# Vorlage_ATmega2560-16AU.net
KiCad netlist of a schematic drawn in EAGLE
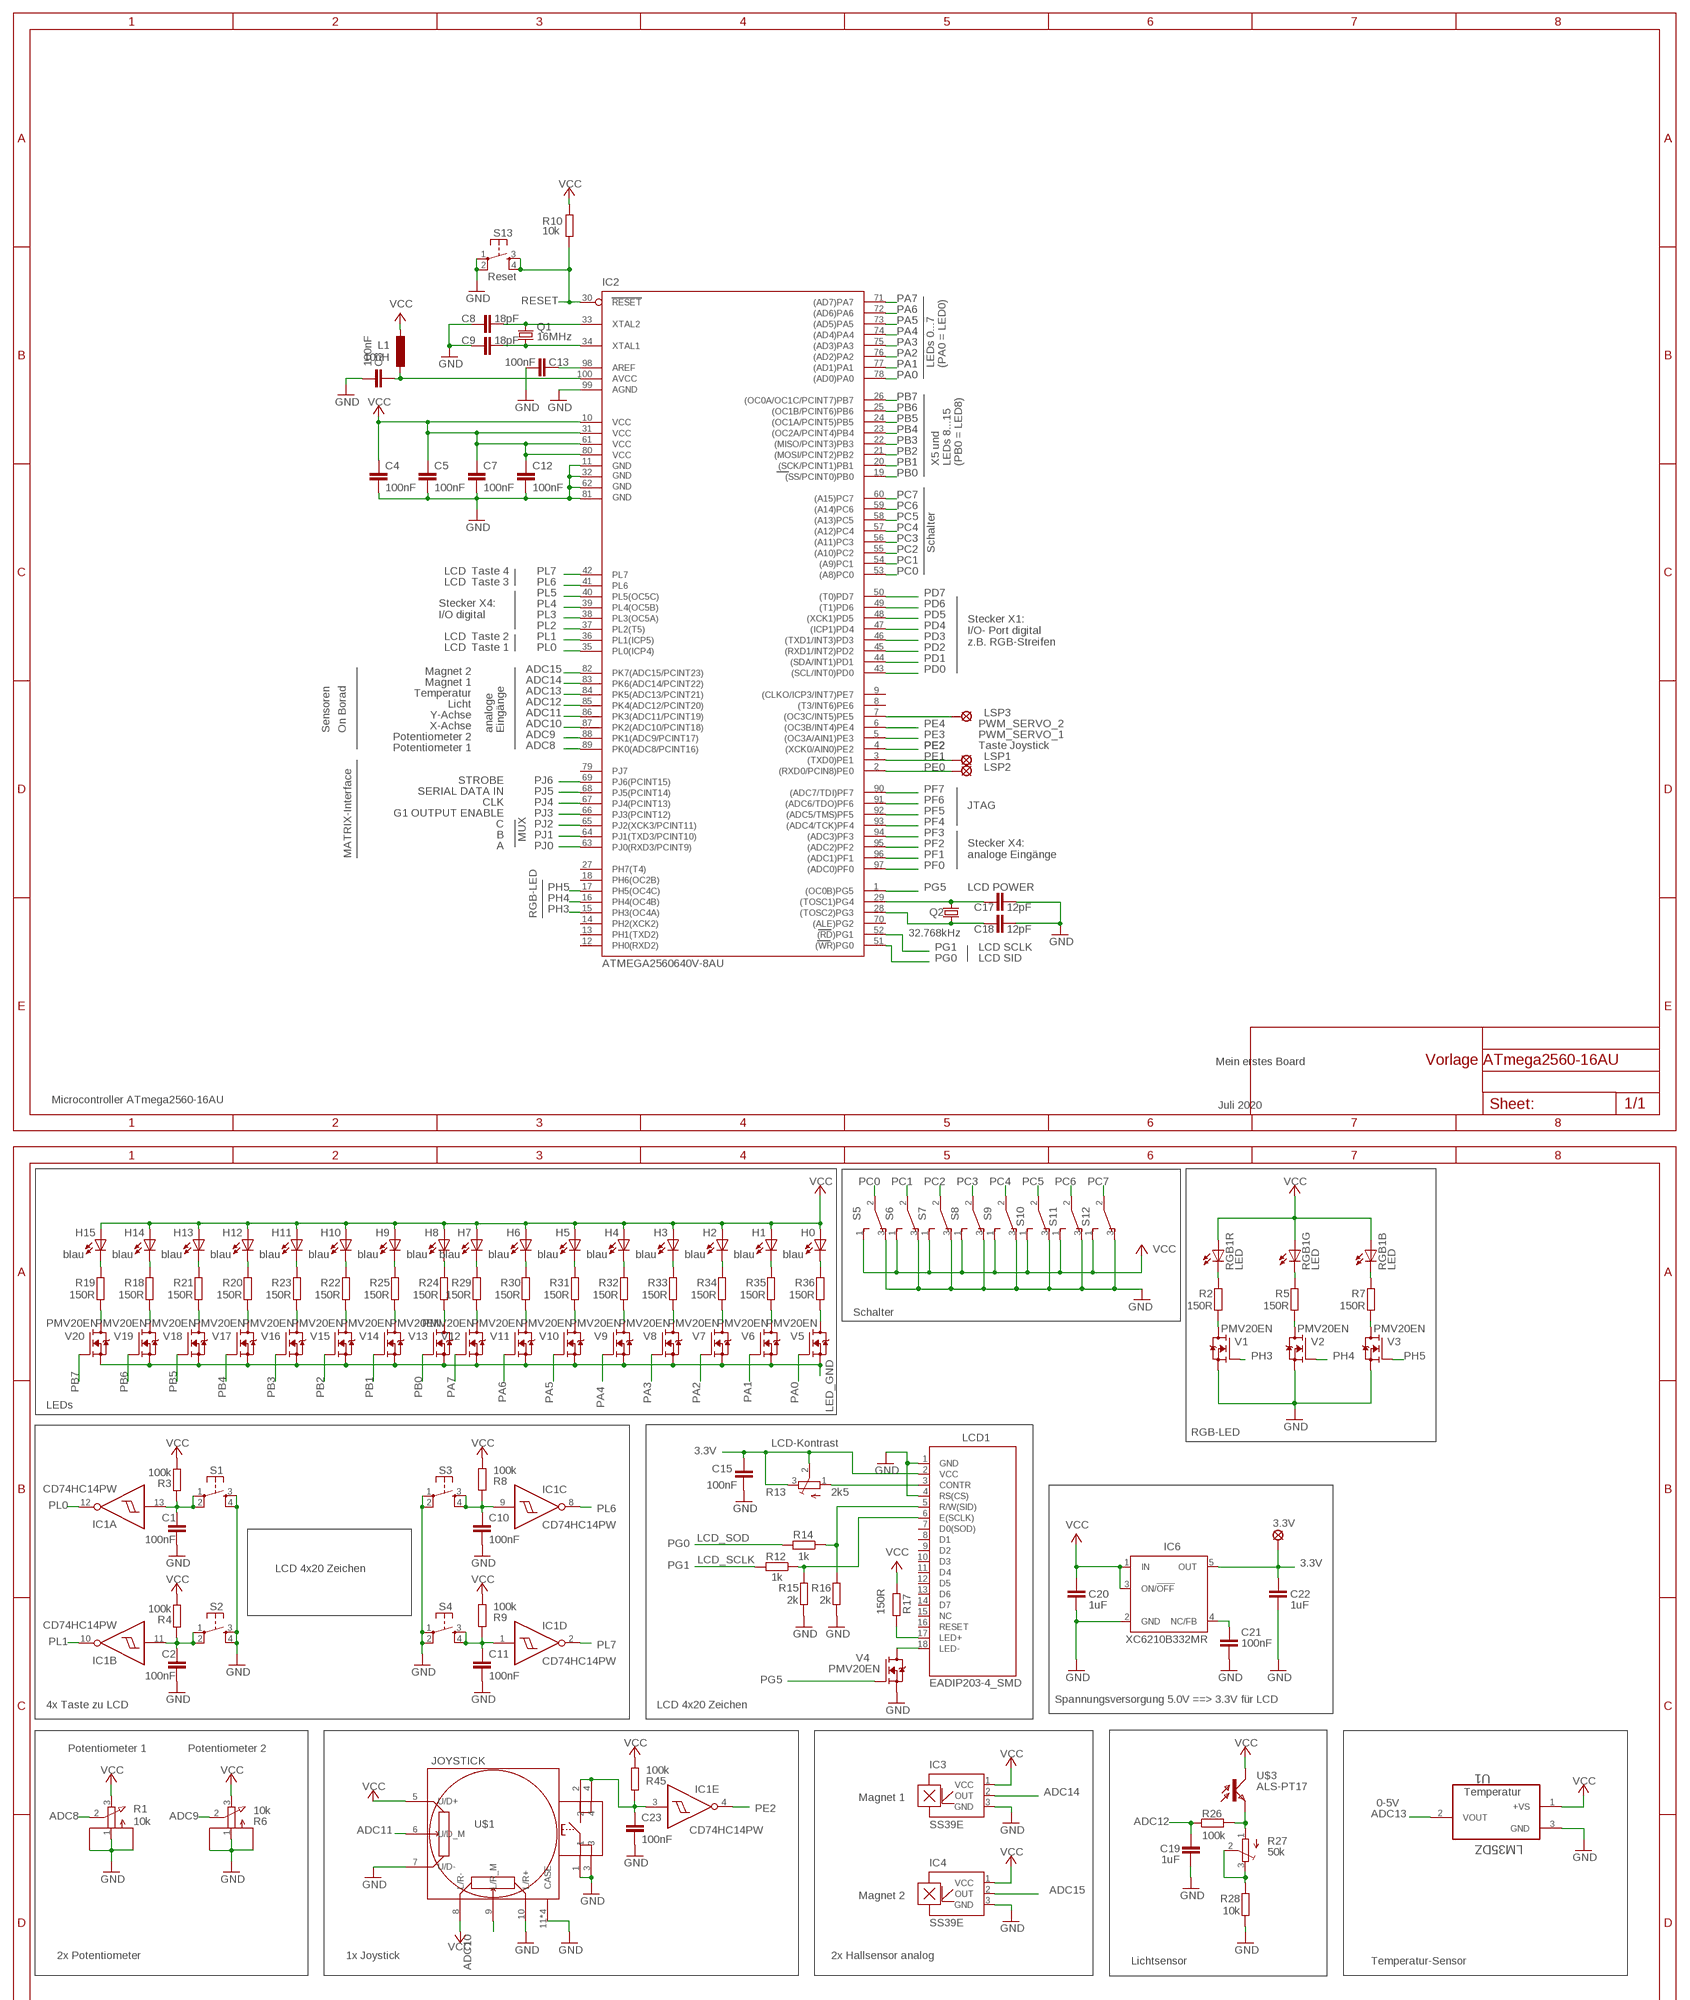
[diagram p0: schematic, sheet 1, part 1 of 2]
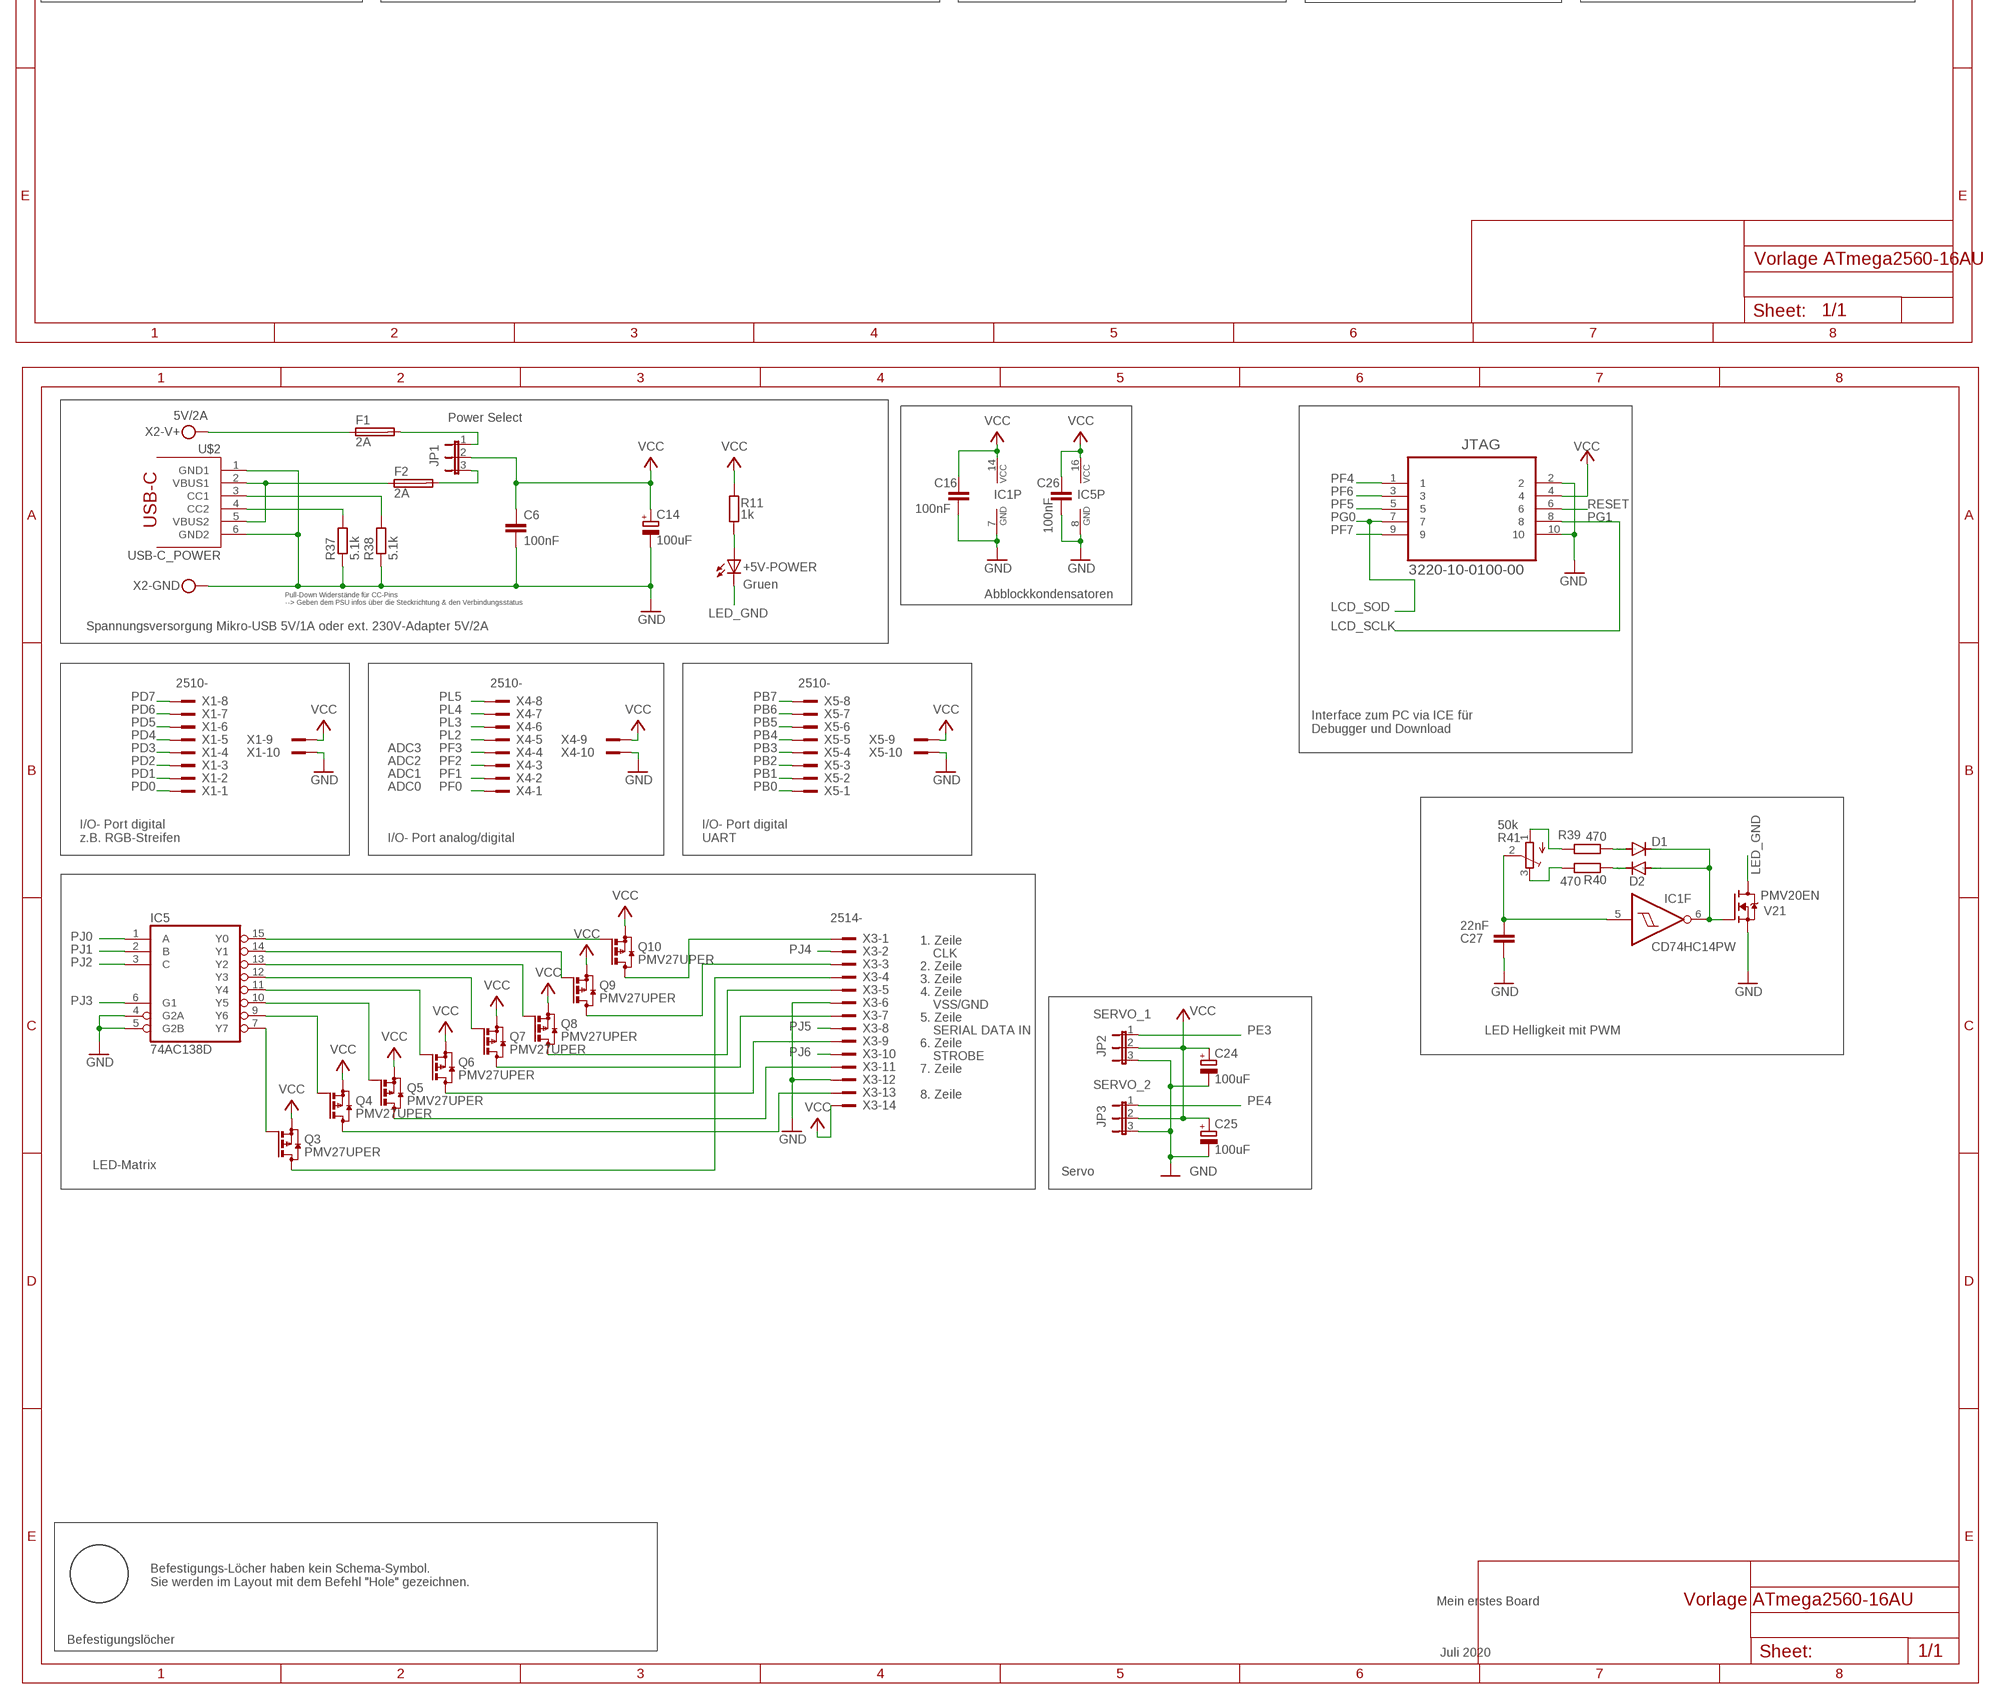
[diagram p1: schematic, sheet 1, part 2 of 2]

(export (version "E")
  (design (tool "Eeschema 10.0.6"))
  (components
    (comp (ref "+5V-POWER")
      (value "Gruen")
      (footprint "eagle-import:CHIPLED_1206")
      (libsource (lib "eagle-import") (part "LEDCHIPLED_1206"))
    )
    (comp (ref "3.3V")
      (value "3.3V")
      (footprint "eagle-import:LSP11")
      (libsource (lib "eagle-import") (part "LSP11"))
    )
    (comp (ref "C1")
      (value "100nF")
      (footprint "eagle-import:C1206")
      (libsource (lib "eagle-import") (part "C-EUC1206"))
    )
    (comp (ref "C2")
      (value "100nF")
      (footprint "eagle-import:C1206")
      (libsource (lib "eagle-import") (part "C-EUC1206"))
    )
    (comp (ref "C3")
      (value "100nF")
      (footprint "eagle-import:C1206")
      (libsource (lib "eagle-import") (part "C-EUC1206"))
    )
    (comp (ref "C4")
      (value "100nF")
      (footprint "eagle-import:C1206")
      (libsource (lib "eagle-import") (part "C-EUC1206"))
    )
    (comp (ref "C5")
      (value "100nF")
      (footprint "eagle-import:C1206")
      (libsource (lib "eagle-import") (part "C-EUC1206"))
    )
    (comp (ref "C6")
      (value "100nF")
      (footprint "eagle-import:C1206")
      (libsource (lib "eagle-import") (part "C-EUC1206"))
    )
    (comp (ref "C7")
      (value "100nF")
      (footprint "eagle-import:C1206")
      (libsource (lib "eagle-import") (part "C-EUC1206"))
    )
    (comp (ref "C8")
      (value "18pF")
      (footprint "eagle-import:C0805K")
      (libsource (lib "eagle-import") (part "C-EUC0805K"))
    )
    (comp (ref "C9")
      (value "18pF")
      (footprint "eagle-import:C0805K")
      (libsource (lib "eagle-import") (part "C-EUC0805K"))
    )
    (comp (ref "C10")
      (value "100nF")
      (footprint "eagle-import:C1206")
      (libsource (lib "eagle-import") (part "C-EUC1206"))
    )
    (comp (ref "C11")
      (value "100nF")
      (footprint "eagle-import:C1206")
      (libsource (lib "eagle-import") (part "C-EUC1206"))
    )
    (comp (ref "C12")
      (value "100nF")
      (footprint "eagle-import:C1206")
      (libsource (lib "eagle-import") (part "C-EUC1206"))
    )
    (comp (ref "C13")
      (value "100nF")
      (footprint "eagle-import:C1206")
      (libsource (lib "eagle-import") (part "C-EUC1206"))
    )
    (comp (ref "C14")
      (value "100uF")
      (footprint "eagle-import:UD-6,3X5,8_NICHICON")
      (libsource (lib "eagle-import") (part "CPOL-EUUD-6,3X8,8"))
    )
    (comp (ref "C15")
      (value "100nF")
      (footprint "eagle-import:C1206")
      (libsource (lib "eagle-import") (part "C-EUC1206"))
    )
    (comp (ref "C16")
      (value "100nF")
      (footprint "eagle-import:C1206")
      (libsource (lib "eagle-import") (part "C-EUC1206"))
    )
    (comp (ref "C17")
      (value "12pF")
      (footprint "eagle-import:C0805K")
      (libsource (lib "eagle-import") (part "C-EUC0805K"))
    )
    (comp (ref "C18")
      (value "12pF")
      (footprint "eagle-import:C0805K")
      (libsource (lib "eagle-import") (part "C-EUC0805K"))
    )
    (comp (ref "C19")
      (value "1uF")
      (footprint "eagle-import:C1206")
      (libsource (lib "eagle-import") (part "C-EUC1206"))
    )
    (comp (ref "C20")
      (value "1uF")
      (footprint "eagle-import:C1206")
      (libsource (lib "eagle-import") (part "C-EUC1206"))
    )
    (comp (ref "C21")
      (value "100nF")
      (footprint "eagle-import:C1206")
      (libsource (lib "eagle-import") (part "C-EUC1206"))
    )
    (comp (ref "C22")
      (value "1uF")
      (footprint "eagle-import:C1206")
      (libsource (lib "eagle-import") (part "C-EUC1206"))
    )
    (comp (ref "C23")
      (value "100nF")
      (footprint "eagle-import:C1206")
      (libsource (lib "eagle-import") (part "C-EUC1206"))
    )
    (comp (ref "C24")
      (value "100uF")
      (footprint "eagle-import:UD-6,3X5,8_NICHICON")
      (libsource (lib "eagle-import") (part "CPOL-EUUD-6,3X8,8"))
    )
    (comp (ref "C25")
      (value "100uF")
      (footprint "eagle-import:UD-6,3X5,8_NICHICON")
      (libsource (lib "eagle-import") (part "CPOL-EUUD-6,3X8,8"))
    )
    (comp (ref "C26")
      (value "100nF")
      (footprint "eagle-import:C1206")
      (libsource (lib "eagle-import") (part "C-EUC1206"))
    )
    (comp (ref "C27")
      (value "22nF")
      (footprint "eagle-import:C0805")
      (libsource (lib "eagle-import") (part "C-EUC0805"))
    )
    (comp (ref "D1")
      (value "DIODE-SOD123")
      (footprint "eagle-import:SOD123")
      (libsource (lib "eagle-import") (part "DIODE-SOD123"))
    )
    (comp (ref "D2")
      (value "DIODE-SOD123")
      (footprint "eagle-import:SOD123")
      (libsource (lib "eagle-import") (part "DIODE-SOD123"))
    )
    (comp (ref "F1")
      (value "2A")
      (footprint "eagle-import:F1206")
      (libsource (lib "eagle-import") (part "195601206"))
    )
    (comp (ref "F2")
      (value "2A")
      (footprint "eagle-import:F1206")
      (libsource (lib "eagle-import") (part "195601206"))
    )
    (comp (ref "H0")
      (value "blau")
      (footprint "eagle-import:CHIPLED_1206")
      (libsource (lib "eagle-import") (part "LEDCHIPLED_1206"))
    )
    (comp (ref "H1")
      (value "blau")
      (footprint "eagle-import:CHIPLED_1206")
      (libsource (lib "eagle-import") (part "LEDCHIPLED_1206"))
    )
    (comp (ref "H2")
      (value "blau")
      (footprint "eagle-import:CHIPLED_1206")
      (libsource (lib "eagle-import") (part "LEDCHIPLED_1206"))
    )
    (comp (ref "H3")
      (value "blau")
      (footprint "eagle-import:CHIPLED_1206")
      (libsource (lib "eagle-import") (part "LEDCHIPLED_1206"))
    )
    (comp (ref "H4")
      (value "blau")
      (footprint "eagle-import:CHIPLED_1206")
      (libsource (lib "eagle-import") (part "LEDCHIPLED_1206"))
    )
    (comp (ref "H5")
      (value "blau")
      (footprint "eagle-import:CHIPLED_1206")
      (libsource (lib "eagle-import") (part "LEDCHIPLED_1206"))
    )
    (comp (ref "H6")
      (value "blau")
      (footprint "eagle-import:CHIPLED_1206")
      (libsource (lib "eagle-import") (part "LEDCHIPLED_1206"))
    )
    (comp (ref "H7")
      (value "blau")
      (footprint "eagle-import:CHIPLED_1206")
      (libsource (lib "eagle-import") (part "LEDCHIPLED_1206"))
    )
    (comp (ref "H8")
      (value "blau")
      (footprint "eagle-import:CHIPLED_1206")
      (libsource (lib "eagle-import") (part "LEDCHIPLED_1206"))
    )
    (comp (ref "H9")
      (value "blau")
      (footprint "eagle-import:CHIPLED_1206")
      (libsource (lib "eagle-import") (part "LEDCHIPLED_1206"))
    )
    (comp (ref "H10")
      (value "blau")
      (footprint "eagle-import:CHIPLED_1206")
      (libsource (lib "eagle-import") (part "LEDCHIPLED_1206"))
    )
    (comp (ref "H11")
      (value "blau")
      (footprint "eagle-import:CHIPLED_1206")
      (libsource (lib "eagle-import") (part "LEDCHIPLED_1206"))
    )
    (comp (ref "H12")
      (value "blau")
      (footprint "eagle-import:CHIPLED_1206")
      (libsource (lib "eagle-import") (part "LEDCHIPLED_1206"))
    )
    (comp (ref "H13")
      (value "blau")
      (footprint "eagle-import:CHIPLED_1206")
      (libsource (lib "eagle-import") (part "LEDCHIPLED_1206"))
    )
    (comp (ref "H14")
      (value "blau")
      (footprint "eagle-import:CHIPLED_1206")
      (libsource (lib "eagle-import") (part "LEDCHIPLED_1206"))
    )
    (comp (ref "H15")
      (value "blau")
      (footprint "eagle-import:CHIPLED_1206")
      (libsource (lib "eagle-import") (part "LEDCHIPLED_1206"))
    )
    (comp (ref "IC1")
      (value "CD74HC14PW")
      (footprint "eagle-import:SO14")
      (libsource (lib "eagle-import") (part "7414D"))
    )
    (comp (ref "IC2")
      (value "ATMEGA2560640V-8AU")
      (footprint "eagle-import:TQFP100")
      (libsource (lib "eagle-import") (part "ATMEGA2560AU640V-8"))
    )
    (comp (ref "IC3")
      (value "SS39E")
      (footprint "eagle-import:SOT23-W")
      (fields (field (name "MF") "ALLEGRO MICROSYSTEMS, INC.") (field (name "MPN") "A1301ELHLT-T"))
      (libsource (lib "eagle-import") (part "A13?LH01"))
    )
    (comp (ref "IC4")
      (value "SS39E")
      (footprint "eagle-import:SOT23-W")
      (fields (field (name "MF") "ALLEGRO MICROSYSTEMS, INC.") (field (name "MPN") "A1301ELHLT-T"))
      (libsource (lib "eagle-import") (part "A13?LH01"))
    )
    (comp (ref "IC5")
      (value "74AC138D")
      (footprint "eagle-import:SO16")
      (libsource (lib "eagle-import") (part "74138DAC"))
    )
    (comp (ref "IC6")
      (value "XC6210B332MR")
      (footprint "eagle-import:SOT23-DBV")
      (libsource (lib "eagle-import") (part "LP2985-XXDBVR"))
    )
    (comp (ref "JP1")
      (value "Power Select")
      (footprint "eagle-import:JP2")
      (libsource (lib "eagle-import") (part "JP2E"))
    )
    (comp (ref "JP2")
      (value "SERVO_1")
      (footprint "eagle-import:JP2")
      (libsource (lib "eagle-import") (part "JP2E"))
    )
    (comp (ref "JP3")
      (value "SERVO_2")
      (footprint "eagle-import:JP2")
      (libsource (lib "eagle-import") (part "JP2E"))
    )
    (comp (ref "JTAG")
      (value "3220-10-0100-00")
      (footprint "eagle-import:SAMTEC_FTS-105-01-L-D")
      (fields (field (name "MPN") "FTS-105-01-L-D"))
      (libsource (lib "eagle-import") (part "FTS-105-01-L-D"))
    )
    (comp (ref "L1")
      (value "10uH")
      (footprint "eagle-import:L2825P")
      (libsource (lib "eagle-import") (part "L-EUL2825P"))
    )
    (comp (ref "LCD1")
      (value "EADIP203-4_SMD")
      (footprint "eagle-import:EADIP203-4SMD")
      (libsource (lib "eagle-import") (part "EADIP203-4EADIP203-4SMD"))
    )
    (comp (ref "LSP1")
      (value "LSP11")
      (footprint "eagle-import:LSP11")
      (libsource (lib "eagle-import") (part "LSP11"))
    )
    (comp (ref "LSP2")
      (value "LSP11")
      (footprint "eagle-import:LSP11")
      (libsource (lib "eagle-import") (part "LSP11"))
    )
    (comp (ref "LSP3")
      (value "LSP11")
      (footprint "eagle-import:LSP11")
      (libsource (lib "eagle-import") (part "LSP11"))
    )
    (comp (ref "Q1")
      (value "16MHz")
      (footprint "eagle-import:HC49UP")
      (libsource (lib "eagle-import") (part "CRYSTALHC49UP"))
    )
    (comp (ref "Q2")
      (value "32.768kHz")
      (footprint "eagle-import:TC38H")
      (libsource (lib "eagle-import") (part "CRYSTALTC38H"))
    )
    (comp (ref "Q3")
      (value "PMV27UPER")
      (footprint "eagle-import:SOT23")
      (libsource (lib "eagle-import") (part "BSS84"))
    )
    (comp (ref "Q4")
      (value "PMV27UPER")
      (footprint "eagle-import:SOT23")
      (libsource (lib "eagle-import") (part "BSS84"))
    )
    (comp (ref "Q5")
      (value "PMV27UPER")
      (footprint "eagle-import:SOT23")
      (libsource (lib "eagle-import") (part "BSS84"))
    )
    (comp (ref "Q6")
      (value "PMV27UPER")
      (footprint "eagle-import:SOT23")
      (libsource (lib "eagle-import") (part "BSS84"))
    )
    (comp (ref "Q7")
      (value "PMV27UPER")
      (footprint "eagle-import:SOT23")
      (libsource (lib "eagle-import") (part "BSS84"))
    )
    (comp (ref "Q8")
      (value "PMV27UPER")
      (footprint "eagle-import:SOT23")
      (libsource (lib "eagle-import") (part "BSS84"))
    )
    (comp (ref "Q9")
      (value "PMV27UPER")
      (footprint "eagle-import:SOT23")
      (libsource (lib "eagle-import") (part "BSS84"))
    )
    (comp (ref "Q10")
      (value "PMV27UPER")
      (footprint "eagle-import:SOT23")
      (libsource (lib "eagle-import") (part "BSS84"))
    )
    (comp (ref "R1")
      (value "10k")
      (footprint "eagle-import:EVUF")
      (libsource (lib "eagle-import") (part "EVUA"))
    )
    (comp (ref "R2")
      (value "150R")
      (footprint "eagle-import:R1206")
      (libsource (lib "eagle-import") (part "rcl_334_R-EU_R1206"))
    )
    (comp (ref "R3")
      (value "100k")
      (footprint "eagle-import:R1206")
      (libsource (lib "eagle-import") (part "rcl_334_R-EU_R1206"))
    )
    (comp (ref "R4")
      (value "100k")
      (footprint "eagle-import:R1206")
      (libsource (lib "eagle-import") (part "rcl_334_R-EU_R1206"))
    )
    (comp (ref "R5")
      (value "150R")
      (footprint "eagle-import:R1206")
      (libsource (lib "eagle-import") (part "rcl_334_R-EU_R1206"))
    )
    (comp (ref "R6")
      (value "10k")
      (footprint "eagle-import:EVUF")
      (libsource (lib "eagle-import") (part "EVUA"))
    )
    (comp (ref "R7")
      (value "150R")
      (footprint "eagle-import:R1206")
      (libsource (lib "eagle-import") (part "rcl_334_R-EU_R1206"))
    )
    (comp (ref "R8")
      (value "100k")
      (footprint "eagle-import:R1206")
      (libsource (lib "eagle-import") (part "rcl_334_R-EU_R1206"))
    )
    (comp (ref "R9")
      (value "100k")
      (footprint "eagle-import:R1206")
      (libsource (lib "eagle-import") (part "rcl_334_R-EU_R1206"))
    )
    (comp (ref "R10")
      (value "10k")
      (footprint "eagle-import:R1206")
      (libsource (lib "eagle-import") (part "rcl_334_R-EU_R1206"))
    )
    (comp (ref "R11")
      (value "1k")
      (footprint "eagle-import:R1206")
      (libsource (lib "eagle-import") (part "rcl_334_R-EU_R1206"))
    )
    (comp (ref "R12")
      (value "1k")
      (footprint "eagle-import:R1206")
      (libsource (lib "eagle-import") (part "rcl_334_R-EU_R1206"))
    )
    (comp (ref "R13")
      (value "2k5")
      (footprint "eagle-import:3223G")
      (libsource (lib "eagle-import") (part "TRIM_EU-3223G"))
    )
    (comp (ref "R14")
      (value "1k")
      (footprint "eagle-import:R1206")
      (libsource (lib "eagle-import") (part "rcl_334_R-EU_R1206"))
    )
    (comp (ref "R15")
      (value "2k")
      (footprint "eagle-import:R1206")
      (libsource (lib "eagle-import") (part "rcl_334_R-EU_R1206"))
    )
    (comp (ref "R16")
      (value "2k")
      (footprint "eagle-import:R1206")
      (libsource (lib "eagle-import") (part "rcl_334_R-EU_R1206"))
    )
    (comp (ref "R17")
      (value "150R")
      (footprint "eagle-import:R1206")
      (libsource (lib "eagle-import") (part "rcl_334_R-EU_R1206"))
    )
    (comp (ref "R18")
      (value "150R")
      (footprint "eagle-import:R1206")
      (libsource (lib "eagle-import") (part "rcl_334_R-EU_R1206"))
    )
    (comp (ref "R19")
      (value "150R")
      (footprint "eagle-import:R1206")
      (libsource (lib "eagle-import") (part "rcl_334_R-EU_R1206"))
    )
    (comp (ref "R20")
      (value "150R")
      (footprint "eagle-import:R1206")
      (libsource (lib "eagle-import") (part "rcl_334_R-EU_R1206"))
    )
    (comp (ref "R21")
      (value "150R")
      (footprint "eagle-import:R1206")
      (libsource (lib "eagle-import") (part "rcl_334_R-EU_R1206"))
    )
    (comp (ref "R22")
      (value "150R")
      (footprint "eagle-import:R1206")
      (libsource (lib "eagle-import") (part "rcl_334_R-EU_R1206"))
    )
    (comp (ref "R23")
      (value "150R")
      (footprint "eagle-import:R1206")
      (libsource (lib "eagle-import") (part "rcl_334_R-EU_R1206"))
    )
    (comp (ref "R24")
      (value "150R")
      (footprint "eagle-import:R1206")
      (libsource (lib "eagle-import") (part "rcl_334_R-EU_R1206"))
    )
    (comp (ref "R25")
      (value "150R")
      (footprint "eagle-import:R1206")
      (libsource (lib "eagle-import") (part "rcl_334_R-EU_R1206"))
    )
    (comp (ref "R26")
      (value "100k")
      (footprint "eagle-import:R1206")
      (libsource (lib "eagle-import") (part "rcl_334_R-EU_R1206"))
    )
    (comp (ref "R27")
      (value "50k")
      (footprint "eagle-import:3223G")
      (libsource (lib "eagle-import") (part "TRIM_EU-3223G"))
    )
    (comp (ref "R28")
      (value "10k")
      (footprint "eagle-import:R1206")
      (libsource (lib "eagle-import") (part "rcl_334_R-EU_R1206"))
    )
    (comp (ref "R29")
      (value "150R")
      (footprint "eagle-import:R1206")
      (libsource (lib "eagle-import") (part "rcl_334_R-EU_R1206"))
    )
    (comp (ref "R30")
      (value "150R")
      (footprint "eagle-import:R1206")
      (libsource (lib "eagle-import") (part "rcl_334_R-EU_R1206"))
    )
    (comp (ref "R31")
      (value "150R")
      (footprint "eagle-import:R1206")
      (libsource (lib "eagle-import") (part "rcl_334_R-EU_R1206"))
    )
    (comp (ref "R32")
      (value "150R")
      (footprint "eagle-import:R1206")
      (libsource (lib "eagle-import") (part "rcl_334_R-EU_R1206"))
    )
    (comp (ref "R33")
      (value "150R")
      (footprint "eagle-import:R1206")
      (libsource (lib "eagle-import") (part "rcl_334_R-EU_R1206"))
    )
    (comp (ref "R34")
      (value "150R")
      (footprint "eagle-import:R1206")
      (libsource (lib "eagle-import") (part "rcl_334_R-EU_R1206"))
    )
    (comp (ref "R35")
      (value "150R")
      (footprint "eagle-import:R1206")
      (libsource (lib "eagle-import") (part "rcl_334_R-EU_R1206"))
    )
    (comp (ref "R36")
      (value "150R")
      (footprint "eagle-import:R1206")
      (libsource (lib "eagle-import") (part "rcl_334_R-EU_R1206"))
    )
    (comp (ref "R37")
      (value "5.1k")
      (footprint "eagle-import:R0805")
      (libsource (lib "eagle-import") (part "R-EU_R0805"))
    )
    (comp (ref "R38")
      (value "5.1k")
      (footprint "eagle-import:R0805")
      (libsource (lib "eagle-import") (part "R-EU_R0805"))
    )
    (comp (ref "R39")
      (value "470")
      (footprint "eagle-import:R0805")
      (libsource (lib "eagle-import") (part "R-EU_R0805"))
    )
    (comp (ref "R40")
      (value "470")
      (footprint "eagle-import:R0805")
      (libsource (lib "eagle-import") (part "R-EU_R0805"))
    )
    (comp (ref "R41")
      (value "50k")
      (footprint "eagle-import:3223G")
      (libsource (lib "eagle-import") (part "TRIM_EU-3223G"))
    )
    (comp (ref "R45")
      (value "100k")
      (footprint "eagle-import:R1206")
      (libsource (lib "eagle-import") (part "rcl_334_R-EU_R1206"))
    )
    (comp (ref "RGB1")
      (value "LED")
      (footprint "eagle-import:LED_MIT_DIFUSOR")
      (libsource (lib "eagle-import") (part "GM5WA94310AMIT_DIFUSOR"))
    )
    (comp (ref "S1")
      (value "TS42_4PAD")
      (footprint "eagle-import:TS42_4PAD")
      (libsource (lib "eagle-import") (part "TS42_4PAD"))
    )
    (comp (ref "S2")
      (value "TS42_4PAD")
      (footprint "eagle-import:TS42_4PAD")
      (libsource (lib "eagle-import") (part "TS42_4PAD"))
    )
    (comp (ref "S3")
      (value "TS42_4PAD")
      (footprint "eagle-import:TS42_4PAD")
      (libsource (lib "eagle-import") (part "TS42_4PAD"))
    )
    (comp (ref "S4")
      (value "TS42_4PAD")
      (footprint "eagle-import:TS42_4PAD")
      (libsource (lib "eagle-import") (part "TS42_4PAD"))
    )
    (comp (ref "S5")
      (value "TL36POSPDT_5MM")
      (footprint "eagle-import:SPDT_5MM")
      (libsource (lib "eagle-import") (part "TL36POSPDT_5MM"))
    )
    (comp (ref "S6")
      (value "TL36POSPDT_5MM")
      (footprint "eagle-import:SPDT_5MM")
      (libsource (lib "eagle-import") (part "TL36POSPDT_5MM"))
    )
    (comp (ref "S7")
      (value "TL36POSPDT_5MM")
      (footprint "eagle-import:SPDT_5MM")
      (libsource (lib "eagle-import") (part "TL36POSPDT_5MM"))
    )
    (comp (ref "S8")
      (value "TL36POSPDT_5MM")
      (footprint "eagle-import:SPDT_5MM")
      (libsource (lib "eagle-import") (part "TL36POSPDT_5MM"))
    )
    (comp (ref "S9")
      (value "TL36POSPDT_5MM")
      (footprint "eagle-import:SPDT_5MM")
      (libsource (lib "eagle-import") (part "TL36POSPDT_5MM"))
    )
    (comp (ref "S10")
      (value "TL36POSPDT_5MM")
      (footprint "eagle-import:SPDT_5MM")
      (libsource (lib "eagle-import") (part "TL36POSPDT_5MM"))
    )
    (comp (ref "S11")
      (value "TL36POSPDT_5MM")
      (footprint "eagle-import:SPDT_5MM")
      (libsource (lib "eagle-import") (part "TL36POSPDT_5MM"))
    )
    (comp (ref "S12")
      (value "TL36POSPDT_5MM")
      (footprint "eagle-import:SPDT_5MM")
      (libsource (lib "eagle-import") (part "TL36POSPDT_5MM"))
    )
    (comp (ref "S13")
      (value "TS42_4PAD")
      (footprint "eagle-import:TS42_4PAD")
      (libsource (lib "eagle-import") (part "TS42_4PAD"))
    )
    (comp (ref "U$1")
      (value "JOYSTICK")
      (footprint "eagle-import:RKJXV1224005")
      (libsource (lib "eagle-import") (part "JOYSTICK"))
    )
    (comp (ref "U$2")
      (value "USB-C_POWER")
      (footprint "eagle-import:USB-C")
      (libsource (lib "eagle-import") (part "USB-C_POWER"))
    )
    (comp (ref "U$3")
      (value "ALS-PT17")
      (footprint "eagle-import:SOD232-W")
      (libsource (lib "eagle-import") (part "ALS-PT17-51C"))
    )
    (comp (ref "U1")
      (value "LM35DZ")
      (footprint "eagle-import:TO127P254X495-3P")
      (libsource (lib "eagle-import") (part "LM35DZ"))
    )
    (comp (ref "V1")
      (value "PMV20EN")
      (footprint "eagle-import:SOT23")
      (libsource (lib "eagle-import") (part "BSS138"))
    )
    (comp (ref "V2")
      (value "PMV20EN")
      (footprint "eagle-import:SOT23")
      (libsource (lib "eagle-import") (part "BSS138"))
    )
    (comp (ref "V3")
      (value "PMV20EN")
      (footprint "eagle-import:SOT23")
      (libsource (lib "eagle-import") (part "BSS138"))
    )
    (comp (ref "V4")
      (value "PMV20EN")
      (footprint "eagle-import:SOT23")
      (libsource (lib "eagle-import") (part "BSS138"))
    )
    (comp (ref "V5")
      (value "PMV20EN")
      (footprint "eagle-import:SOT23")
      (libsource (lib "eagle-import") (part "BSS138"))
    )
    (comp (ref "V6")
      (value "PMV20EN")
      (footprint "eagle-import:SOT23")
      (libsource (lib "eagle-import") (part "BSS138"))
    )
    (comp (ref "V7")
      (value "PMV20EN")
      (footprint "eagle-import:SOT23")
      (libsource (lib "eagle-import") (part "BSS138"))
    )
    (comp (ref "V8")
      (value "PMV20EN")
      (footprint "eagle-import:SOT23")
      (libsource (lib "eagle-import") (part "BSS138"))
    )
    (comp (ref "V9")
      (value "PMV20EN")
      (footprint "eagle-import:SOT23")
      (libsource (lib "eagle-import") (part "BSS138"))
    )
    (comp (ref "V10")
      (value "PMV20EN")
      (footprint "eagle-import:SOT23")
      (libsource (lib "eagle-import") (part "BSS138"))
    )
    (comp (ref "V11")
      (value "PMV20EN")
      (footprint "eagle-import:SOT23")
      (libsource (lib "eagle-import") (part "BSS138"))
    )
    (comp (ref "V12")
      (value "PMV20EN")
      (footprint "eagle-import:SOT23")
      (libsource (lib "eagle-import") (part "BSS138"))
    )
    (comp (ref "V13")
      (value "PMV20EN")
      (footprint "eagle-import:SOT23")
      (libsource (lib "eagle-import") (part "BSS138"))
    )
    (comp (ref "V14")
      (value "PMV20EN")
      (footprint "eagle-import:SOT23")
      (libsource (lib "eagle-import") (part "BSS138"))
    )
    (comp (ref "V15")
      (value "PMV20EN")
      (footprint "eagle-import:SOT23")
      (libsource (lib "eagle-import") (part "BSS138"))
    )
    (comp (ref "V16")
      (value "PMV20EN")
      (footprint "eagle-import:SOT23")
      (libsource (lib "eagle-import") (part "BSS138"))
    )
    (comp (ref "V17")
      (value "PMV20EN")
      (footprint "eagle-import:SOT23")
      (libsource (lib "eagle-import") (part "BSS138"))
    )
    (comp (ref "V18")
      (value "PMV20EN")
      (footprint "eagle-import:SOT23")
      (libsource (lib "eagle-import") (part "BSS138"))
    )
    (comp (ref "V19")
      (value "PMV20EN")
      (footprint "eagle-import:SOT23")
      (libsource (lib "eagle-import") (part "BSS138"))
    )
    (comp (ref "V20")
      (value "PMV20EN")
      (footprint "eagle-import:SOT23")
      (libsource (lib "eagle-import") (part "BSS138"))
    )
    (comp (ref "V21")
      (value "PMV20EN")
      (footprint "eagle-import:SOT23")
      (libsource (lib "eagle-import") (part "BSS138"))
    )
    (comp (ref "X1")
      (value "2510-")
      (footprint "eagle-import:PAK100_2500-10")
      (fields (field (name "MF") "3M") (field (name "MPN") "2510-6002UB"))
      (libsource (lib "eagle-import") (part "2510-"))
    )
    (comp (ref "X2")
      (value "+5V")
      (footprint "eagle-import:MKDSN1,5_2-5,08")
      (fields (field (name "MPN") "MKDSN 1,5/2-5.08"))
      (libsource (lib "eagle-import") (part "MKDSN1,5/2-5,08"))
    )
    (comp (ref "X3")
      (value "2514-")
      (footprint "eagle-import:PAK100_2500-14")
      (libsource (lib "eagle-import") (part "2514-"))
    )
    (comp (ref "X4")
      (value "2510-")
      (footprint "eagle-import:PAK100_2500-10")
      (fields (field (name "MF") "3M") (field (name "MPN") "2510-6002UB"))
      (libsource (lib "eagle-import") (part "2510-"))
    )
    (comp (ref "X5")
      (value "2510-")
      (footprint "eagle-import:PAK100_2500-10")
      (fields (field (name "MF") "3M") (field (name "MPN") "2510-6002UB"))
      (libsource (lib "eagle-import") (part "2510-"))
    )
  )
  (nets
    (net (code "1") (name "/3.3V") (class "Default")
      (node (ref "3.3V") (pin "MP") (pinfunction "MP_MP") (pintype "passive"))
      (node (ref "C15") (pin "1") (pinfunction "1_1") (pintype "passive"))
      (node (ref "C22") (pin "1") (pinfunction "1_1") (pintype "passive"))
      (node (ref "IC6") (pin "5") (pinfunction "OUT_5") (pintype "passive"))
      (node (ref "LCD1") (pin "2") (pinfunction "VCC_2") (pintype "passive"))
      (node (ref "R13") (pin "2") (pinfunction "S_2") (pintype "passive"))
      (node (ref "R13") (pin "3") (pinfunction "E_3") (pintype "passive"))
    )
    (net (code "2") (name "/ADC8") (class "Default")
      (node (ref "IC2") (pin "89") (pinfunction "PK0(ADC8/PCINT16)_89") (pintype "bidirectional"))
      (node (ref "R1") (pin "2") (pinfunction "S_2") (pintype "passive"))
    )
    (net (code "3") (name "/ADC9") (class "Default")
      (node (ref "IC2") (pin "88") (pinfunction "PK1(ADC9/PCINT17)_88") (pintype "bidirectional"))
      (node (ref "R6") (pin "2") (pinfunction "S_2") (pintype "passive"))
    )
    (net (code "4") (name "/ADC10") (class "Default")
      (node (ref "IC2") (pin "87") (pinfunction "PK2(ADC10/PCINT18)_87") (pintype "bidirectional"))
      (node (ref "U$1") (pin "9") (pinfunction "L/R_M_9") (pintype "bidirectional"))
    )
    (net (code "5") (name "/ADC11") (class "Default")
      (node (ref "IC2") (pin "86") (pinfunction "PK3(ADC11/PCINT19)_86") (pintype "bidirectional"))
      (node (ref "U$1") (pin "6") (pinfunction "U/D_M_6") (pintype "bidirectional"))
    )
    (net (code "6") (name "/ADC12") (class "Default")
      (node (ref "C19") (pin "2") (pinfunction "2_2") (pintype "passive"))
      (node (ref "IC2") (pin "85") (pinfunction "PK4(ADC12/PCINT20)_85") (pintype "bidirectional"))
      (node (ref "R26") (pin "1") (pinfunction "1_1") (pintype "passive"))
    )
    (net (code "7") (name "/ADC13") (class "Default")
      (node (ref "IC2") (pin "84") (pinfunction "PK5(ADC13/PCINT21)_84") (pintype "bidirectional"))
      (node (ref "U1") (pin "2") (pinfunction "VOUT_2") (pintype "output"))
    )
    (net (code "8") (name "/ADC14") (class "Default")
      (node (ref "IC2") (pin "83") (pinfunction "PK6(ADC14/PCINT22)_83") (pintype "bidirectional"))
      (node (ref "IC3") (pin "2") (pinfunction "OUT_2") (pintype "output"))
    )
    (net (code "9") (name "/ADC15") (class "Default")
      (node (ref "IC2") (pin "82") (pinfunction "PK7(ADC15/PCINT23)_82") (pintype "bidirectional"))
      (node (ref "IC4") (pin "2") (pinfunction "OUT_2") (pintype "output"))
    )
    (net (code "10") (name "/LED_GND") (class "Default")
      (node (ref "+5V-POWER") (pin "C") (pinfunction "C_C") (pintype "passive"))
      (node (ref "V10") (pin "2") (pinfunction "S_2") (pintype "passive"))
      (node (ref "V11") (pin "2") (pinfunction "S_2") (pintype "passive"))
      (node (ref "V12") (pin "2") (pinfunction "S_2") (pintype "passive"))
      (node (ref "V13") (pin "2") (pinfunction "S_2") (pintype "passive"))
      (node (ref "V14") (pin "2") (pinfunction "S_2") (pintype "passive"))
      (node (ref "V15") (pin "2") (pinfunction "S_2") (pintype "passive"))
      (node (ref "V16") (pin "2") (pinfunction "S_2") (pintype "passive"))
      (node (ref "V17") (pin "2") (pinfunction "S_2") (pintype "passive"))
      (node (ref "V18") (pin "2") (pinfunction "S_2") (pintype "passive"))
      (node (ref "V19") (pin "2") (pinfunction "S_2") (pintype "passive"))
      (node (ref "V20") (pin "2") (pinfunction "S_2") (pintype "passive"))
      (node (ref "V21") (pin "3") (pinfunction "D_3") (pintype "passive"))
      (node (ref "V5") (pin "2") (pinfunction "S_2") (pintype "passive"))
      (node (ref "V6") (pin "2") (pinfunction "S_2") (pintype "passive"))
      (node (ref "V7") (pin "2") (pinfunction "S_2") (pintype "passive"))
      (node (ref "V8") (pin "2") (pinfunction "S_2") (pintype "passive"))
      (node (ref "V9") (pin "2") (pinfunction "S_2") (pintype "passive"))
    )
    (net (code "11") (name "/PA0") (class "Default")
      (node (ref "IC2") (pin "78") (pinfunction "(AD0)PA0_78") (pintype "bidirectional"))
      (node (ref "V5") (pin "1") (pinfunction "G_1") (pintype "passive"))
    )
    (net (code "12") (name "/PA1") (class "Default")
      (node (ref "IC2") (pin "77") (pinfunction "(AD1)PA1_77") (pintype "bidirectional"))
      (node (ref "V6") (pin "1") (pinfunction "G_1") (pintype "passive"))
    )
    (net (code "13") (name "/PA2") (class "Default")
      (node (ref "IC2") (pin "76") (pinfunction "(AD2)PA2_76") (pintype "bidirectional"))
      (node (ref "V7") (pin "1") (pinfunction "G_1") (pintype "passive"))
    )
    (net (code "14") (name "/PA3") (class "Default")
      (node (ref "IC2") (pin "75") (pinfunction "(AD3)PA3_75") (pintype "bidirectional"))
      (node (ref "V8") (pin "1") (pinfunction "G_1") (pintype "passive"))
    )
    (net (code "15") (name "/PA4") (class "Default")
      (node (ref "IC2") (pin "74") (pinfunction "(AD4)PA4_74") (pintype "bidirectional"))
      (node (ref "V9") (pin "1") (pinfunction "G_1") (pintype "passive"))
    )
    (net (code "16") (name "/PA5") (class "Default")
      (node (ref "IC2") (pin "73") (pinfunction "(AD5)PA5_73") (pintype "bidirectional"))
      (node (ref "V10") (pin "1") (pinfunction "G_1") (pintype "passive"))
    )
    (net (code "17") (name "/PA6") (class "Default")
      (node (ref "IC2") (pin "72") (pinfunction "(AD6)PA6_72") (pintype "bidirectional"))
      (node (ref "V11") (pin "1") (pinfunction "G_1") (pintype "passive"))
    )
    (net (code "18") (name "/PA7") (class "Default")
      (node (ref "IC2") (pin "71") (pinfunction "(AD7)PA7_71") (pintype "bidirectional"))
      (node (ref "V12") (pin "1") (pinfunction "G_1") (pintype "passive"))
    )
    (net (code "19") (name "/PB0") (class "Default")
      (node (ref "IC2") (pin "19") (pinfunction "(SS/PCINT0)PB0_19") (pintype "bidirectional"))
      (node (ref "V13") (pin "1") (pinfunction "G_1") (pintype "passive"))
      (node (ref "X5") (pin "1") (pinfunction "KL_1") (pintype "passive"))
    )
    (net (code "20") (name "/PB1") (class "Default")
      (node (ref "IC2") (pin "20") (pinfunction "(SCK/PCINT1)PB1_20") (pintype "bidirectional"))
      (node (ref "V14") (pin "1") (pinfunction "G_1") (pintype "passive"))
      (node (ref "X5") (pin "2") (pinfunction "KL_2") (pintype "passive"))
    )
    (net (code "21") (name "/PB2") (class "Default")
      (node (ref "IC2") (pin "21") (pinfunction "(MOSI/PCINT2)PB2_21") (pintype "bidirectional"))
      (node (ref "V15") (pin "1") (pinfunction "G_1") (pintype "passive"))
      (node (ref "X5") (pin "3") (pinfunction "KL_3") (pintype "passive"))
    )
    (net (code "22") (name "/PB3") (class "Default")
      (node (ref "IC2") (pin "22") (pinfunction "(MISO/PCINT3)PB3_22") (pintype "bidirectional"))
      (node (ref "V16") (pin "1") (pinfunction "G_1") (pintype "passive"))
      (node (ref "X5") (pin "4") (pinfunction "KL_4") (pintype "passive"))
    )
    (net (code "23") (name "/PB4") (class "Default")
      (node (ref "IC2") (pin "23") (pinfunction "(OC2A/PCINT4)PB4_23") (pintype "bidirectional"))
      (node (ref "V17") (pin "1") (pinfunction "G_1") (pintype "passive"))
      (node (ref "X5") (pin "5") (pinfunction "KL_5") (pintype "passive"))
    )
    (net (code "24") (name "/PB5") (class "Default")
      (node (ref "IC2") (pin "24") (pinfunction "(OC1A/PCINT5)PB5_24") (pintype "bidirectional"))
      (node (ref "V18") (pin "1") (pinfunction "G_1") (pintype "passive"))
      (node (ref "X5") (pin "6") (pinfunction "KL_6") (pintype "passive"))
    )
    (net (code "25") (name "/PB6") (class "Default")
      (node (ref "IC2") (pin "25") (pinfunction "(OC1B/PCINT6)PB6_25") (pintype "bidirectional"))
      (node (ref "V19") (pin "1") (pinfunction "G_1") (pintype "passive"))
      (node (ref "X5") (pin "7") (pinfunction "KL_7") (pintype "passive"))
    )
    (net (code "26") (name "/PB7") (class "Default")
      (node (ref "IC2") (pin "26") (pinfunction "(OC0A/OC1C/PCINT7)PB7_26") (pintype "bidirectional"))
      (node (ref "V20") (pin "1") (pinfunction "G_1") (pintype "passive"))
      (node (ref "X5") (pin "8") (pinfunction "KL_8") (pintype "passive"))
    )
    (net (code "27") (name "/PC0") (class "Default")
      (node (ref "IC2") (pin "53") (pinfunction "(A8)PC0_53") (pintype "bidirectional"))
      (node (ref "S5") (pin "2") (pinfunction "P_2") (pintype "passive"))
    )
    (net (code "28") (name "/PC1") (class "Default")
      (node (ref "IC2") (pin "54") (pinfunction "(A9)PC1_54") (pintype "bidirectional"))
      (node (ref "S6") (pin "2") (pinfunction "P_2") (pintype "passive"))
    )
    (net (code "29") (name "/PC2") (class "Default")
      (node (ref "IC2") (pin "55") (pinfunction "(A10)PC2_55") (pintype "bidirectional"))
      (node (ref "S7") (pin "2") (pinfunction "P_2") (pintype "passive"))
    )
    (net (code "30") (name "/PC3") (class "Default")
      (node (ref "IC2") (pin "56") (pinfunction "(A11)PC3_56") (pintype "bidirectional"))
      (node (ref "S8") (pin "2") (pinfunction "P_2") (pintype "passive"))
    )
    (net (code "31") (name "/PC4") (class "Default")
      (node (ref "IC2") (pin "57") (pinfunction "(A12)PC4_57") (pintype "bidirectional"))
      (node (ref "S9") (pin "2") (pinfunction "P_2") (pintype "passive"))
    )
    (net (code "32") (name "/PC5") (class "Default")
      (node (ref "IC2") (pin "58") (pinfunction "(A13)PC5_58") (pintype "bidirectional"))
      (node (ref "S10") (pin "2") (pinfunction "P_2") (pintype "passive"))
    )
    (net (code "33") (name "/PC6") (class "Default")
      (node (ref "IC2") (pin "59") (pinfunction "(A14)PC6_59") (pintype "bidirectional"))
      (node (ref "S11") (pin "2") (pinfunction "P_2") (pintype "passive"))
    )
    (net (code "34") (name "/PC7") (class "Default")
      (node (ref "IC2") (pin "60") (pinfunction "(A15)PC7_60") (pintype "bidirectional"))
      (node (ref "S12") (pin "2") (pinfunction "P_2") (pintype "passive"))
    )
    (net (code "35") (name "/PD0") (class "Default")
      (node (ref "IC2") (pin "43") (pinfunction "(SCL/INT0)PD0_43") (pintype "bidirectional"))
      (node (ref "X1") (pin "1") (pinfunction "KL_1") (pintype "passive"))
    )
    (net (code "36") (name "/PD1") (class "Default")
      (node (ref "IC2") (pin "44") (pinfunction "(SDA/INT1)PD1_44") (pintype "bidirectional"))
      (node (ref "X1") (pin "2") (pinfunction "KL_2") (pintype "passive"))
    )
    (net (code "37") (name "/PD2") (class "Default")
      (node (ref "IC2") (pin "45") (pinfunction "(RXD1/INT2)PD2_45") (pintype "bidirectional"))
      (node (ref "X1") (pin "3") (pinfunction "KL_3") (pintype "passive"))
    )
    (net (code "38") (name "/PD3") (class "Default")
      (node (ref "IC2") (pin "46") (pinfunction "(TXD1/INT3)PD3_46") (pintype "bidirectional"))
      (node (ref "X1") (pin "4") (pinfunction "KL_4") (pintype "passive"))
    )
    (net (code "39") (name "/PD4") (class "Default")
      (node (ref "IC2") (pin "47") (pinfunction "(ICP1)PD4_47") (pintype "bidirectional"))
      (node (ref "X1") (pin "5") (pinfunction "KL_5") (pintype "passive"))
    )
    (net (code "40") (name "/PD5") (class "Default")
      (node (ref "IC2") (pin "48") (pinfunction "(XCK1)PD5_48") (pintype "bidirectional"))
      (node (ref "X1") (pin "6") (pinfunction "KL_6") (pintype "passive"))
    )
    (net (code "41") (name "/PD6") (class "Default")
      (node (ref "IC2") (pin "49") (pinfunction "(T1)PD6_49") (pintype "bidirectional"))
      (node (ref "X1") (pin "7") (pinfunction "KL_7") (pintype "passive"))
    )
    (net (code "42") (name "/PD7") (class "Default")
      (node (ref "IC2") (pin "50") (pinfunction "(T0)PD7_50") (pintype "bidirectional"))
      (node (ref "X1") (pin "8") (pinfunction "KL_8") (pintype "passive"))
    )
    (net (code "43") (name "/PE0") (class "Default")
      (node (ref "IC2") (pin "2") (pinfunction "(RXD0/PCIN8)PE0_2") (pintype "bidirectional"))
      (node (ref "LSP2") (pin "MP") (pinfunction "MP_MP") (pintype "passive"))
    )
    (net (code "44") (name "/PE1") (class "Default")
      (node (ref "IC2") (pin "3") (pinfunction "(TXD0)PE1_3") (pintype "bidirectional"))
      (node (ref "LSP1") (pin "MP") (pinfunction "MP_MP") (pintype "passive"))
    )
    (net (code "45") (name "/PE2") (class "Default")
      (node (ref "IC1") (pin "4") (pinfunction "O_4") (pintype "output"))
      (node (ref "IC2") (pin "4") (pinfunction "(XCK0/AIN0)PE2_4") (pintype "bidirectional"))
    )
    (net (code "46") (name "/PE3") (class "Default")
      (node (ref "IC2") (pin "5") (pinfunction "(OC3A/AIN1)PE3_5") (pintype "bidirectional"))
      (node (ref "JP2") (pin "1") (pinfunction "1_1") (pintype "passive"))
    )
    (net (code "47") (name "/PE4") (class "Default")
      (node (ref "IC2") (pin "6") (pinfunction "(OC3B/INT4)PE4_6") (pintype "bidirectional"))
      (node (ref "JP3") (pin "1") (pinfunction "1_1") (pintype "passive"))
    )
    (net (code "48") (name "/PF0") (class "Default")
      (node (ref "IC2") (pin "97") (pinfunction "(ADC0)PF0_97") (pintype "bidirectional"))
      (node (ref "X4") (pin "1") (pinfunction "KL_1") (pintype "passive"))
    )
    (net (code "49") (name "/PF1") (class "Default")
      (node (ref "IC2") (pin "96") (pinfunction "(ADC1)PF1_96") (pintype "bidirectional"))
      (node (ref "X4") (pin "2") (pinfunction "KL_2") (pintype "passive"))
    )
    (net (code "50") (name "/PF2") (class "Default")
      (node (ref "IC2") (pin "95") (pinfunction "(ADC2)PF2_95") (pintype "bidirectional"))
      (node (ref "X4") (pin "3") (pinfunction "KL_3") (pintype "passive"))
    )
    (net (code "51") (name "/PF3") (class "Default")
      (node (ref "IC2") (pin "94") (pinfunction "(ADC3)PF3_94") (pintype "bidirectional"))
      (node (ref "X4") (pin "4") (pinfunction "KL_4") (pintype "passive"))
    )
    (net (code "52") (name "/PF4") (class "Default")
      (node (ref "IC2") (pin "93") (pinfunction "(ADC4/TCK)PF4_93") (pintype "bidirectional"))
      (node (ref "JTAG") (pin "1") (pinfunction "1_1") (pintype "passive"))
    )
    (net (code "53") (name "/PF5") (class "Default")
      (node (ref "IC2") (pin "92") (pinfunction "(ADC5/TMS)PF5_92") (pintype "bidirectional"))
      (node (ref "JTAG") (pin "5") (pinfunction "5_5") (pintype "passive"))
    )
    (net (code "54") (name "/PF6") (class "Default")
      (node (ref "IC2") (pin "91") (pinfunction "(ADC6/TDO)PF6_91") (pintype "bidirectional"))
      (node (ref "JTAG") (pin "3") (pinfunction "3_3") (pintype "passive"))
    )
    (net (code "55") (name "/PF7") (class "Default")
      (node (ref "IC2") (pin "90") (pinfunction "(ADC7/TDI)PF7_90") (pintype "bidirectional"))
      (node (ref "JTAG") (pin "9") (pinfunction "9_9") (pintype "passive"))
    )
    (net (code "56") (name "/PG0") (class "Default")
      (node (ref "IC2") (pin "51") (pinfunction "(WR)PG0_51") (pintype "bidirectional"))
      (node (ref "JTAG") (pin "7") (pinfunction "7_7") (pintype "passive"))
      (node (ref "R14") (pin "2") (pinfunction "2_2") (pintype "passive"))
    )
    (net (code "57") (name "/PG1") (class "Default")
      (node (ref "IC2") (pin "52") (pinfunction "(RD)PG1_52") (pintype "bidirectional"))
      (node (ref "JTAG") (pin "8") (pinfunction "8_8") (pintype "passive"))
      (node (ref "R12") (pin "2") (pinfunction "2_2") (pintype "passive"))
    )
    (net (code "58") (name "/PG5") (class "Default")
      (node (ref "IC2") (pin "1") (pinfunction "(OC0B)PG5_1") (pintype "bidirectional"))
      (node (ref "V4") (pin "1") (pinfunction "G_1") (pintype "passive"))
    )
    (net (code "59") (name "/PH3") (class "Default")
      (node (ref "IC2") (pin "15") (pinfunction "PH3(OC4A)_15") (pintype "bidirectional"))
      (node (ref "V1") (pin "1") (pinfunction "G_1") (pintype "passive"))
    )
    (net (code "60") (name "/PH4") (class "Default")
      (node (ref "IC2") (pin "16") (pinfunction "PH4(OC4B)_16") (pintype "bidirectional"))
      (node (ref "V2") (pin "1") (pinfunction "G_1") (pintype "passive"))
    )
    (net (code "61") (name "/PH5") (class "Default")
      (node (ref "IC2") (pin "17") (pinfunction "PH5(OC4C)_17") (pintype "bidirectional"))
      (node (ref "V3") (pin "1") (pinfunction "G_1") (pintype "passive"))
    )
    (net (code "62") (name "/PJ0") (class "Default")
      (node (ref "IC2") (pin "63") (pinfunction "PJ0(RXD3/PCINT9)_63") (pintype "bidirectional"))
      (node (ref "IC5") (pin "1") (pinfunction "A_1") (pintype "input"))
    )
    (net (code "63") (name "/PJ1") (class "Default")
      (node (ref "IC2") (pin "64") (pinfunction "PJ1(TXD3/PCINT10)_64") (pintype "bidirectional"))
      (node (ref "IC5") (pin "2") (pinfunction "B_2") (pintype "input"))
    )
    (net (code "64") (name "/PJ2") (class "Default")
      (node (ref "IC2") (pin "65") (pinfunction "PJ2(XCK3/PCINT11)_65") (pintype "bidirectional"))
      (node (ref "IC5") (pin "3") (pinfunction "C_3") (pintype "input"))
    )
    (net (code "65") (name "/PJ3") (class "Default")
      (node (ref "IC2") (pin "66") (pinfunction "PJ3(PCINT12)_66") (pintype "bidirectional"))
      (node (ref "IC5") (pin "6") (pinfunction "G1_6") (pintype "input"))
    )
    (net (code "66") (name "/PJ4") (class "Default")
      (node (ref "IC2") (pin "67") (pinfunction "PJ4(PCINT13)_67") (pintype "bidirectional"))
      (node (ref "X3") (pin "2") (pinfunction "KL_2") (pintype "passive"))
    )
    (net (code "67") (name "/PJ5") (class "Default")
      (node (ref "IC2") (pin "68") (pinfunction "PJ5(PCINT14)_68") (pintype "bidirectional"))
      (node (ref "X3") (pin "8") (pinfunction "KL_8") (pintype "passive"))
    )
    (net (code "68") (name "/PJ6") (class "Default")
      (node (ref "IC2") (pin "69") (pinfunction "PJ6(PCINT15)_69") (pintype "bidirectional"))
      (node (ref "X3") (pin "10") (pinfunction "KL_10") (pintype "passive"))
    )
    (net (code "69") (name "/PL0") (class "Default")
      (node (ref "IC1") (pin "12") (pinfunction "O_12") (pintype "output"))
      (node (ref "IC2") (pin "35") (pinfunction "PL0(ICP4)_35") (pintype "bidirectional"))
    )
    (net (code "70") (name "/PL1") (class "Default")
      (node (ref "IC1") (pin "10") (pinfunction "O_10") (pintype "output"))
      (node (ref "IC2") (pin "36") (pinfunction "PL1(ICP5)_36") (pintype "bidirectional"))
    )
    (net (code "71") (name "/PL2") (class "Default")
      (node (ref "IC2") (pin "37") (pinfunction "PL2(T5)_37") (pintype "bidirectional"))
      (node (ref "X4") (pin "5") (pinfunction "KL_5") (pintype "passive"))
    )
    (net (code "72") (name "/PL3") (class "Default")
      (node (ref "IC2") (pin "38") (pinfunction "PL3(OC5A)_38") (pintype "bidirectional"))
      (node (ref "X4") (pin "6") (pinfunction "KL_6") (pintype "passive"))
    )
    (net (code "73") (name "/PL4") (class "Default")
      (node (ref "IC2") (pin "39") (pinfunction "PL4(OC5B)_39") (pintype "bidirectional"))
      (node (ref "X4") (pin "7") (pinfunction "KL_7") (pintype "passive"))
    )
    (net (code "74") (name "/PL5") (class "Default")
      (node (ref "IC2") (pin "40") (pinfunction "PL5(OC5C)_40") (pintype "bidirectional"))
      (node (ref "X4") (pin "8") (pinfunction "KL_8") (pintype "passive"))
    )
    (net (code "75") (name "/PL6") (class "Default")
      (node (ref "IC1") (pin "8") (pinfunction "O_8") (pintype "output"))
      (node (ref "IC2") (pin "41") (pinfunction "PL6_41") (pintype "bidirectional"))
    )
    (net (code "76") (name "/PL7") (class "Default")
      (node (ref "IC1") (pin "2") (pinfunction "O_2") (pintype "output"))
      (node (ref "IC2") (pin "42") (pinfunction "PL7_42") (pintype "bidirectional"))
    )
    (net (code "77") (name "/RESET") (class "Default")
      (node (ref "IC2") (pin "30") (pinfunction "RESET_30") (pintype "input"))
      (node (ref "JTAG") (pin "6") (pinfunction "6_6") (pintype "passive"))
      (node (ref "R10") (pin "1") (pinfunction "1_1") (pintype "passive"))
      (node (ref "S13") (pin "3") (pinfunction "3_3") (pintype "passive"))
      (node (ref "S13") (pin "4") (pinfunction "4_4") (pintype "passive"))
    )
    (net (code "78") (name "GND") (class "Default")
      (node (ref "C1") (pin "2") (pinfunction "2_2") (pintype "passive"))
      (node (ref "C10") (pin "2") (pinfunction "2_2") (pintype "passive"))
      (node (ref "C11") (pin "2") (pinfunction "2_2") (pintype "passive"))
      (node (ref "C12") (pin "2") (pinfunction "2_2") (pintype "passive"))
      (node (ref "C13") (pin "1") (pinfunction "1_1") (pintype "passive"))
      (node (ref "C14") (pin "-") (pinfunction "-_-") (pintype "passive"))
      (node (ref "C15") (pin "2") (pinfunction "2_2") (pintype "passive"))
      (node (ref "C16") (pin "2") (pinfunction "2_2") (pintype "passive"))
      (node (ref "C17") (pin "2") (pinfunction "2_2") (pintype "passive"))
      (node (ref "C18") (pin "2") (pinfunction "2_2") (pintype "passive"))
      (node (ref "C19") (pin "1") (pinfunction "1_1") (pintype "passive"))
      (node (ref "C2") (pin "2") (pinfunction "2_2") (pintype "passive"))
      (node (ref "C20") (pin "2") (pinfunction "2_2") (pintype "passive"))
      (node (ref "C21") (pin "2") (pinfunction "2_2") (pintype "passive"))
      (node (ref "C22") (pin "2") (pinfunction "2_2") (pintype "passive"))
      (node (ref "C23") (pin "2") (pinfunction "2_2") (pintype "passive"))
      (node (ref "C24") (pin "-") (pinfunction "-_-") (pintype "passive"))
      (node (ref "C25") (pin "-") (pinfunction "-_-") (pintype "passive"))
      (node (ref "C26") (pin "2") (pinfunction "2_2") (pintype "passive"))
      (node (ref "C27") (pin "2") (pinfunction "2_2") (pintype "passive"))
      (node (ref "C3") (pin "1") (pinfunction "1_1") (pintype "passive"))
      (node (ref "C4") (pin "2") (pinfunction "2_2") (pintype "passive"))
      (node (ref "C5") (pin "2") (pinfunction "2_2") (pintype "passive"))
      (node (ref "C6") (pin "2") (pinfunction "2_2") (pintype "passive"))
      (node (ref "C7") (pin "2") (pinfunction "2_2") (pintype "passive"))
      (node (ref "C8") (pin "1") (pinfunction "1_1") (pintype "passive"))
      (node (ref "C9") (pin "2") (pinfunction "2_2") (pintype "passive"))
      (node (ref "IC1") (pin "7") (pinfunction "GND_7") (pintype "power_in"))
      (node (ref "IC2") (pin "11") (pinfunction "GND_11") (pintype "power_in"))
      (node (ref "IC2") (pin "32") (pinfunction "GND1_32") (pintype "power_in"))
      (node (ref "IC2") (pin "62") (pinfunction "GND2_62") (pintype "power_in"))
      (node (ref "IC2") (pin "81") (pinfunction "GND3_81") (pintype "power_in"))
      (node (ref "IC2") (pin "99") (pinfunction "AGND_99") (pintype "power_in"))
      (node (ref "IC3") (pin "3") (pinfunction "GND_3") (pintype "power_in"))
      (node (ref "IC4") (pin "3") (pinfunction "GND_3") (pintype "power_in"))
      (node (ref "IC5") (pin "4") (pinfunction "G2A_4") (pintype "input"))
      (node (ref "IC5") (pin "5") (pinfunction "G2B_5") (pintype "input"))
      (node (ref "IC5") (pin "8") (pinfunction "GND_8") (pintype "power_in"))
      (node (ref "IC6") (pin "2") (pinfunction "GND_2") (pintype "power_in"))
      (node (ref "JP2") (pin "3") (pinfunction "3_3") (pintype "passive"))
      (node (ref "JP3") (pin "3") (pinfunction "3_3") (pintype "passive"))
      (node (ref "JTAG") (pin "10") (pinfunction "10_10") (pintype "passive"))
      (node (ref "JTAG") (pin "2") (pinfunction "2_2") (pintype "passive"))
      (node (ref "LCD1") (pin "1") (pinfunction "GND_1") (pintype "power_in"))
      (node (ref "LCD1") (pin "4") (pinfunction "RS(CS)_4") (pintype "input"))
      (node (ref "R1") (pin "1") (pinfunction "A_1") (pintype "passive"))
      (node (ref "R1") (pin "M1") (pinfunction "P$1_M1") (pintype "bidirectional"))
      (node (ref "R1") (pin "M2") (pinfunction "P$2_M2") (pintype "bidirectional"))
      (node (ref "R15") (pin "1") (pinfunction "1_1") (pintype "passive"))
      (node (ref "R16") (pin "1") (pinfunction "1_1") (pintype "passive"))
      (node (ref "R28") (pin "1") (pinfunction "1_1") (pintype "passive"))
      (node (ref "R37") (pin "1") (pinfunction "1_1") (pintype "passive"))
      (node (ref "R38") (pin "1") (pinfunction "1_1") (pintype "passive"))
      (node (ref "R6") (pin "1") (pinfunction "A_1") (pintype "passive"))
      (node (ref "R6") (pin "M1") (pinfunction "P$1_M1") (pintype "bidirectional"))
      (node (ref "R6") (pin "M2") (pinfunction "P$2_M2") (pintype "bidirectional"))
      (node (ref "S1") (pin "3") (pinfunction "3_3") (pintype "passive"))
      (node (ref "S1") (pin "4") (pinfunction "4_4") (pintype "passive"))
      (node (ref "S10") (pin "3") (pinfunction "O_3") (pintype "passive"))
      (node (ref "S11") (pin "3") (pinfunction "O_3") (pintype "passive"))
      (node (ref "S12") (pin "3") (pinfunction "O_3") (pintype "passive"))
      (node (ref "S13") (pin "1") (pinfunction "1_1") (pintype "passive"))
      (node (ref "S13") (pin "2") (pinfunction "2_2") (pintype "passive"))
      (node (ref "S2") (pin "3") (pinfunction "3_3") (pintype "passive"))
      (node (ref "S2") (pin "4") (pinfunction "4_4") (pintype "passive"))
      (node (ref "S3") (pin "1") (pinfunction "1_1") (pintype "passive"))
      (node (ref "S3") (pin "2") (pinfunction "2_2") (pintype "passive"))
      (node (ref "S4") (pin "1") (pinfunction "1_1") (pintype "passive"))
      (node (ref "S4") (pin "2") (pinfunction "2_2") (pintype "passive"))
      (node (ref "S5") (pin "3") (pinfunction "O_3") (pintype "passive"))
      (node (ref "S6") (pin "3") (pinfunction "O_3") (pintype "passive"))
      (node (ref "S7") (pin "3") (pinfunction "O_3") (pintype "passive"))
      (node (ref "S8") (pin "3") (pinfunction "O_3") (pintype "passive"))
      (node (ref "S9") (pin "3") (pinfunction "O_3") (pintype "passive"))
      (node (ref "U$1") (pin "1") (pinfunction "1_1") (pintype "bidirectional"))
      (node (ref "U$1") (pin "10") (pinfunction "L/R+_10") (pintype "bidirectional"))
      (node (ref "U$1") (pin "11") (pinfunction "CASE_11") (pintype "bidirectional"))
      (node (ref "U$1") (pin "12") (pinfunction "CASE_12") (pintype "bidirectional"))
      (node (ref "U$1") (pin "15") (pinfunction "CASE_15") (pintype "bidirectional"))
      (node (ref "U$1") (pin "16") (pinfunction "CASE_16") (pintype "bidirectional"))
      (node (ref "U$1") (pin "3") (pinfunction "3_3") (pintype "bidirectional"))
      (node (ref "U$1") (pin "7") (pinfunction "U/D-_7") (pintype "bidirectional"))
      (node (ref "U$2") (pin "1") (pinfunction "GND1_1") (pintype "bidirectional"))
      (node (ref "U$2") (pin "6") (pinfunction "GND2_6") (pintype "bidirectional"))
      (node (ref "U1") (pin "3") (pinfunction "GND_3") (pintype "passive"))
      (node (ref "V1") (pin "2") (pinfunction "S_2") (pintype "passive"))
      (node (ref "V2") (pin "2") (pinfunction "S_2") (pintype "passive"))
      (node (ref "V21") (pin "2") (pinfunction "S_2") (pintype "passive"))
      (node (ref "V3") (pin "2") (pinfunction "S_2") (pintype "passive"))
      (node (ref "V4") (pin "2") (pinfunction "S_2") (pintype "passive"))
      (node (ref "X1") (pin "10") (pinfunction "KL_10") (pintype "passive"))
      (node (ref "X2") (pin "1.1") (pinfunction "KL_1.1") (pintype "passive"))
      (node (ref "X2") (pin "1.2") (pinfunction "KL_1.2") (pintype "passive"))
      (node (ref "X3") (pin "12") (pinfunction "KL_12") (pintype "passive"))
      (node (ref "X3") (pin "6") (pinfunction "KL_6") (pintype "passive"))
      (node (ref "X4") (pin "10") (pinfunction "KL_10") (pintype "passive"))
      (node (ref "X5") (pin "10") (pinfunction "KL_10") (pintype "passive"))
    )
    (net (code "79") (name "Net-(+5V-POWER-PadA)") (class "Default")
      (node (ref "+5V-POWER") (pin "A") (pinfunction "A_A") (pintype "passive"))
      (node (ref "R11") (pin "1") (pinfunction "1_1") (pintype "passive"))
    )
    (net (code "80") (name "Net-(D1-PadA)") (class "Default")
      (node (ref "D1") (pin "A") (pinfunction "A_A") (pintype "passive"))
      (node (ref "R39") (pin "1") (pinfunction "1_1") (pintype "passive"))
    )
    (net (code "81") (name "Net-(D2-PadC)") (class "Default")
      (node (ref "D2") (pin "C") (pinfunction "C_C") (pintype "passive"))
      (node (ref "R40") (pin "1") (pinfunction "1_1") (pintype "passive"))
    )
    (net (code "82") (name "Net-(F1-Pad1)") (class "Default")
      (node (ref "F1") (pin "1") (pinfunction "1_1") (pintype "passive"))
      (node (ref "X2") (pin "2.1") (pinfunction "KL_2.1") (pintype "passive"))
      (node (ref "X2") (pin "2.2") (pinfunction "KL_2.2") (pintype "passive"))
    )
    (net (code "83") (name "Net-(F1-Pad2)") (class "Default")
      (node (ref "F1") (pin "2") (pinfunction "2_2") (pintype "passive"))
      (node (ref "JP1") (pin "1") (pinfunction "1_1") (pintype "passive"))
    )
    (net (code "84") (name "Net-(F2-Pad2)") (class "Default")
      (node (ref "F2") (pin "2") (pinfunction "2_2") (pintype "passive"))
      (node (ref "JP1") (pin "3") (pinfunction "3_3") (pintype "passive"))
    )
    (net (code "85") (name "Net-(H0-PadC)") (class "Default")
      (node (ref "H0") (pin "C") (pinfunction "C_C") (pintype "passive"))
      (node (ref "R36") (pin "2") (pinfunction "2_2") (pintype "passive"))
    )
    (net (code "86") (name "Net-(H1-PadC)") (class "Default")
      (node (ref "H1") (pin "C") (pinfunction "C_C") (pintype "passive"))
      (node (ref "R35") (pin "2") (pinfunction "2_2") (pintype "passive"))
    )
    (net (code "87") (name "Net-(H2-PadC)") (class "Default")
      (node (ref "H2") (pin "C") (pinfunction "C_C") (pintype "passive"))
      (node (ref "R34") (pin "2") (pinfunction "2_2") (pintype "passive"))
    )
    (net (code "88") (name "Net-(H3-PadC)") (class "Default")
      (node (ref "H3") (pin "C") (pinfunction "C_C") (pintype "passive"))
      (node (ref "R33") (pin "2") (pinfunction "2_2") (pintype "passive"))
    )
    (net (code "89") (name "Net-(H4-PadC)") (class "Default")
      (node (ref "H4") (pin "C") (pinfunction "C_C") (pintype "passive"))
      (node (ref "R32") (pin "2") (pinfunction "2_2") (pintype "passive"))
    )
    (net (code "90") (name "Net-(H5-PadC)") (class "Default")
      (node (ref "H5") (pin "C") (pinfunction "C_C") (pintype "passive"))
      (node (ref "R31") (pin "2") (pinfunction "2_2") (pintype "passive"))
    )
    (net (code "91") (name "Net-(H6-PadC)") (class "Default")
      (node (ref "H6") (pin "C") (pinfunction "C_C") (pintype "passive"))
      (node (ref "R30") (pin "2") (pinfunction "2_2") (pintype "passive"))
    )
    (net (code "92") (name "Net-(H7-PadC)") (class "Default")
      (node (ref "H7") (pin "C") (pinfunction "C_C") (pintype "passive"))
      (node (ref "R29") (pin "2") (pinfunction "2_2") (pintype "passive"))
    )
    (net (code "93") (name "Net-(H8-PadC)") (class "Default")
      (node (ref "H8") (pin "C") (pinfunction "C_C") (pintype "passive"))
      (node (ref "R24") (pin "2") (pinfunction "2_2") (pintype "passive"))
    )
    (net (code "94") (name "Net-(H9-PadC)") (class "Default")
      (node (ref "H9") (pin "C") (pinfunction "C_C") (pintype "passive"))
      (node (ref "R25") (pin "2") (pinfunction "2_2") (pintype "passive"))
    )
    (net (code "95") (name "Net-(H10-PadC)") (class "Default")
      (node (ref "H10") (pin "C") (pinfunction "C_C") (pintype "passive"))
      (node (ref "R22") (pin "2") (pinfunction "2_2") (pintype "passive"))
    )
    (net (code "96") (name "Net-(H11-PadC)") (class "Default")
      (node (ref "H11") (pin "C") (pinfunction "C_C") (pintype "passive"))
      (node (ref "R23") (pin "2") (pinfunction "2_2") (pintype "passive"))
    )
    (net (code "97") (name "Net-(H12-PadC)") (class "Default")
      (node (ref "H12") (pin "C") (pinfunction "C_C") (pintype "passive"))
      (node (ref "R20") (pin "2") (pinfunction "2_2") (pintype "passive"))
    )
    (net (code "98") (name "Net-(H13-PadC)") (class "Default")
      (node (ref "H13") (pin "C") (pinfunction "C_C") (pintype "passive"))
      (node (ref "R21") (pin "2") (pinfunction "2_2") (pintype "passive"))
    )
    (net (code "99") (name "Net-(H14-PadC)") (class "Default")
      (node (ref "H14") (pin "C") (pinfunction "C_C") (pintype "passive"))
      (node (ref "R18") (pin "2") (pinfunction "2_2") (pintype "passive"))
    )
    (net (code "100") (name "Net-(H15-PadC)") (class "Default")
      (node (ref "H15") (pin "C") (pinfunction "C_C") (pintype "passive"))
      (node (ref "R19") (pin "2") (pinfunction "2_2") (pintype "passive"))
    )
    (net (code "101") (name "Net-(IC1A-I)") (class "Default")
      (node (ref "C1") (pin "1") (pinfunction "1_1") (pintype "passive"))
      (node (ref "IC1") (pin "13") (pinfunction "I_13") (pintype "input"))
      (node (ref "R3") (pin "2") (pinfunction "2_2") (pintype "passive"))
      (node (ref "S1") (pin "1") (pinfunction "1_1") (pintype "passive"))
      (node (ref "S1") (pin "2") (pinfunction "2_2") (pintype "passive"))
    )
    (net (code "102") (name "Net-(IC1B-I)") (class "Default")
      (node (ref "C2") (pin "1") (pinfunction "1_1") (pintype "passive"))
      (node (ref "IC1") (pin "11") (pinfunction "I_11") (pintype "input"))
      (node (ref "R4") (pin "2") (pinfunction "2_2") (pintype "passive"))
      (node (ref "S2") (pin "1") (pinfunction "1_1") (pintype "passive"))
      (node (ref "S2") (pin "2") (pinfunction "2_2") (pintype "passive"))
    )
    (net (code "103") (name "Net-(IC1C-I)") (class "Default")
      (node (ref "C10") (pin "1") (pinfunction "1_1") (pintype "passive"))
      (node (ref "IC1") (pin "9") (pinfunction "I_9") (pintype "input"))
      (node (ref "R8") (pin "1") (pinfunction "1_1") (pintype "passive"))
      (node (ref "S3") (pin "3") (pinfunction "3_3") (pintype "passive"))
      (node (ref "S3") (pin "4") (pinfunction "4_4") (pintype "passive"))
    )
    (net (code "104") (name "Net-(IC1D-I)") (class "Default")
      (node (ref "C11") (pin "1") (pinfunction "1_1") (pintype "passive"))
      (node (ref "IC1") (pin "1") (pinfunction "I_1") (pintype "input"))
      (node (ref "R9") (pin "1") (pinfunction "1_1") (pintype "passive"))
      (node (ref "S4") (pin "3") (pinfunction "3_3") (pintype "passive"))
      (node (ref "S4") (pin "4") (pinfunction "4_4") (pintype "passive"))
    )
    (net (code "105") (name "Net-(IC1E-I)") (class "Default")
      (node (ref "C23") (pin "1") (pinfunction "1_1") (pintype "passive"))
      (node (ref "IC1") (pin "3") (pinfunction "I_3") (pintype "input"))
      (node (ref "R45") (pin "1") (pinfunction "1_1") (pintype "passive"))
      (node (ref "U$1") (pin "2") (pinfunction "2_2") (pintype "bidirectional"))
      (node (ref "U$1") (pin "4") (pinfunction "4_4") (pintype "bidirectional"))
    )
    (net (code "106") (name "Net-(IC1F-I)") (class "Default")
      (node (ref "C27") (pin "1") (pinfunction "1_1") (pintype "passive"))
      (node (ref "IC1") (pin "5") (pinfunction "I_5") (pintype "input"))
      (node (ref "R41") (pin "2") (pinfunction "S_2") (pintype "passive"))
    )
    (net (code "107") (name "Net-(IC1F-O)") (class "Default")
      (node (ref "D1") (pin "C") (pinfunction "C_C") (pintype "passive"))
      (node (ref "D2") (pin "A") (pinfunction "A_A") (pintype "passive"))
      (node (ref "IC1") (pin "6") (pinfunction "O_6") (pintype "output"))
      (node (ref "V21") (pin "1") (pinfunction "G_1") (pintype "passive"))
    )
    (net (code "108") (name "Net-(IC2-(OC3C{slash}INT5)PE5)") (class "Default")
      (node (ref "IC2") (pin "7") (pinfunction "(OC3C/INT5)PE5_7") (pintype "bidirectional"))
      (node (ref "LSP3") (pin "MP") (pinfunction "MP_MP") (pintype "passive"))
    )
    (net (code "109") (name "Net-(IC2-(TOSC1)PG4)") (class "Default")
      (node (ref "C17") (pin "1") (pinfunction "1_1") (pintype "passive"))
      (node (ref "IC2") (pin "29") (pinfunction "(TOSC1)PG4_29") (pintype "bidirectional"))
      (node (ref "Q2") (pin "1") (pinfunction "1_1") (pintype "passive"))
    )
    (net (code "110") (name "Net-(IC2-(TOSC2)PG3)") (class "Default")
      (node (ref "C18") (pin "1") (pinfunction "1_1") (pintype "passive"))
      (node (ref "IC2") (pin "28") (pinfunction "(TOSC2)PG3_28") (pintype "bidirectional"))
      (node (ref "Q2") (pin "2") (pinfunction "2_2") (pintype "passive"))
    )
    (net (code "111") (name "Net-(IC2-AREF)") (class "Default")
      (node (ref "C13") (pin "2") (pinfunction "2_2") (pintype "passive"))
      (node (ref "IC2") (pin "98") (pinfunction "AREF_98") (pintype "bidirectional"))
    )
    (net (code "112") (name "Net-(IC2-AVCC)") (class "Default")
      (node (ref "C3") (pin "2") (pinfunction "2_2") (pintype "passive"))
      (node (ref "IC2") (pin "100") (pinfunction "AVCC_100") (pintype "power_in"))
      (node (ref "L1") (pin "2") (pinfunction "2_2") (pintype "passive"))
    )
    (net (code "113") (name "Net-(IC2-XTAL1)") (class "Default")
      (node (ref "C9") (pin "1") (pinfunction "1_1") (pintype "passive"))
      (node (ref "IC2") (pin "34") (pinfunction "XTAL1_34") (pintype "input"))
      (node (ref "Q1") (pin "1") (pinfunction "1_1") (pintype "passive"))
    )
    (net (code "114") (name "Net-(IC2-XTAL2)") (class "Default")
      (node (ref "C8") (pin "2") (pinfunction "2_2") (pintype "passive"))
      (node (ref "IC2") (pin "33") (pinfunction "XTAL2_33") (pintype "output"))
      (node (ref "Q1") (pin "2") (pinfunction "2_2") (pintype "passive"))
    )
    (net (code "115") (name "Net-(IC5A-Y0)") (class "Default")
      (node (ref "IC5") (pin "15") (pinfunction "Y0_15") (pintype "output"))
      (node (ref "Q10") (pin "1") (pinfunction "G_1") (pintype "passive"))
    )
    (net (code "116") (name "Net-(IC5A-Y1)") (class "Default")
      (node (ref "IC5") (pin "14") (pinfunction "Y1_14") (pintype "output"))
      (node (ref "Q9") (pin "1") (pinfunction "G_1") (pintype "passive"))
    )
    (net (code "117") (name "Net-(IC5A-Y2)") (class "Default")
      (node (ref "IC5") (pin "13") (pinfunction "Y2_13") (pintype "output"))
      (node (ref "Q8") (pin "1") (pinfunction "G_1") (pintype "passive"))
    )
    (net (code "118") (name "Net-(IC5A-Y3)") (class "Default")
      (node (ref "IC5") (pin "12") (pinfunction "Y3_12") (pintype "output"))
      (node (ref "Q7") (pin "1") (pinfunction "G_1") (pintype "passive"))
    )
    (net (code "119") (name "Net-(IC5A-Y4)") (class "Default")
      (node (ref "IC5") (pin "11") (pinfunction "Y4_11") (pintype "output"))
      (node (ref "Q6") (pin "1") (pinfunction "G_1") (pintype "passive"))
    )
    (net (code "120") (name "Net-(IC5A-Y5)") (class "Default")
      (node (ref "IC5") (pin "10") (pinfunction "Y5_10") (pintype "output"))
      (node (ref "Q5") (pin "1") (pinfunction "G_1") (pintype "passive"))
    )
    (net (code "121") (name "Net-(IC5A-Y6)") (class "Default")
      (node (ref "IC5") (pin "9") (pinfunction "Y6_9") (pintype "output"))
      (node (ref "Q4") (pin "1") (pinfunction "G_1") (pintype "passive"))
    )
    (net (code "122") (name "Net-(IC5A-Y7)") (class "Default")
      (node (ref "IC5") (pin "7") (pinfunction "Y7_7") (pintype "output"))
      (node (ref "Q3") (pin "1") (pinfunction "G_1") (pintype "passive"))
    )
    (net (code "123") (name "Net-(IC6-NC{slash}FB)") (class "Default")
      (node (ref "C21") (pin "1") (pinfunction "1_1") (pintype "passive"))
      (node (ref "IC6") (pin "4") (pinfunction "NC/FB_4") (pintype "passive"))
    )
    (net (code "124") (name "Net-(LCD1-CONTR)") (class "Default")
      (node (ref "LCD1") (pin "3") (pinfunction "CONTR_3") (pintype "input"))
      (node (ref "R13") (pin "1") (pinfunction "A_1") (pintype "passive"))
    )
    (net (code "125") (name "Net-(LCD1-E(SCLK))") (class "Default")
      (node (ref "LCD1") (pin "6") (pinfunction "E(SCLK)_6") (pintype "input"))
      (node (ref "R12") (pin "1") (pinfunction "1_1") (pintype "passive"))
      (node (ref "R15") (pin "2") (pinfunction "2_2") (pintype "passive"))
    )
    (net (code "126") (name "Net-(LCD1-LED+)") (class "Default")
      (node (ref "LCD1") (pin "17") (pinfunction "LED+_17") (pintype "passive"))
      (node (ref "R17") (pin "1") (pinfunction "1_1") (pintype "passive"))
    )
    (net (code "127") (name "Net-(LCD1-LED-)") (class "Default")
      (node (ref "LCD1") (pin "18") (pinfunction "LED-_18") (pintype "passive"))
      (node (ref "V4") (pin "3") (pinfunction "D_3") (pintype "passive"))
    )
    (net (code "128") (name "Net-(LCD1-R{slash}W(SID))") (class "Default")
      (node (ref "LCD1") (pin "5") (pinfunction "R/W(SID)_5") (pintype "input"))
      (node (ref "R14") (pin "1") (pinfunction "1_1") (pintype "passive"))
      (node (ref "R16") (pin "2") (pinfunction "2_2") (pintype "passive"))
    )
    (net (code "129") (name "Net-(Q3-D)") (class "Default")
      (node (ref "Q3") (pin "3") (pinfunction "D_3") (pintype "passive"))
      (node (ref "X3") (pin "4") (pinfunction "KL_4") (pintype "passive"))
    )
    (net (code "130") (name "Net-(Q4-D)") (class "Default")
      (node (ref "Q4") (pin "3") (pinfunction "D_3") (pintype "passive"))
      (node (ref "X3") (pin "13") (pinfunction "KL_13") (pintype "passive"))
    )
    (net (code "131") (name "Net-(Q5-D)") (class "Default")
      (node (ref "Q5") (pin "3") (pinfunction "D_3") (pintype "passive"))
      (node (ref "X3") (pin "11") (pinfunction "KL_11") (pintype "passive"))
    )
    (net (code "132") (name "Net-(Q6-D)") (class "Default")
      (node (ref "Q6") (pin "3") (pinfunction "D_3") (pintype "passive"))
      (node (ref "X3") (pin "9") (pinfunction "KL_9") (pintype "passive"))
    )
    (net (code "133") (name "Net-(Q7-D)") (class "Default")
      (node (ref "Q7") (pin "3") (pinfunction "D_3") (pintype "passive"))
      (node (ref "X3") (pin "7") (pinfunction "KL_7") (pintype "passive"))
    )
    (net (code "134") (name "Net-(Q8-D)") (class "Default")
      (node (ref "Q8") (pin "3") (pinfunction "D_3") (pintype "passive"))
      (node (ref "X3") (pin "5") (pinfunction "KL_5") (pintype "passive"))
    )
    (net (code "135") (name "Net-(Q9-D)") (class "Default")
      (node (ref "Q9") (pin "3") (pinfunction "D_3") (pintype "passive"))
      (node (ref "X3") (pin "3") (pinfunction "KL_3") (pintype "passive"))
    )
    (net (code "136") (name "Net-(Q10-D)") (class "Default")
      (node (ref "Q10") (pin "3") (pinfunction "D_3") (pintype "passive"))
      (node (ref "X3") (pin "1") (pinfunction "KL_1") (pintype "passive"))
    )
    (net (code "137") (name "Net-(R27-A)") (class "Default")
      (node (ref "R26") (pin "2") (pinfunction "2_2") (pintype "passive"))
      (node (ref "R27") (pin "1") (pinfunction "A_1") (pintype "passive"))
      (node (ref "U$3") (pin "E") (pinfunction "E_E") (pintype "passive"))
    )
    (net (code "138") (name "Net-(R27-E)") (class "Default")
      (node (ref "R27") (pin "2") (pinfunction "S_2") (pintype "passive"))
      (node (ref "R27") (pin "3") (pinfunction "E_3") (pintype "passive"))
      (node (ref "R28") (pin "2") (pinfunction "2_2") (pintype "passive"))
    )
    (net (code "139") (name "Net-(R41-A)") (class "Default")
      (node (ref "R39") (pin "2") (pinfunction "2_2") (pintype "passive"))
      (node (ref "R41") (pin "1") (pinfunction "A_1") (pintype "passive"))
    )
    (net (code "140") (name "Net-(R41-E)") (class "Default")
      (node (ref "R40") (pin "2") (pinfunction "2_2") (pintype "passive"))
      (node (ref "R41") (pin "3") (pinfunction "E_3") (pintype "passive"))
    )
    (net (code "141") (name "Net-(RGB1A-C)") (class "Default")
      (node (ref "R7") (pin "2") (pinfunction "2_2") (pintype "passive"))
      (node (ref "RGB1") (pin "1") (pinfunction "C_1") (pintype "passive"))
    )
    (net (code "142") (name "Net-(RGB1B-C)") (class "Default")
      (node (ref "R5") (pin "2") (pinfunction "2_2") (pintype "passive"))
      (node (ref "RGB1") (pin "2") (pinfunction "C_2") (pintype "passive"))
    )
    (net (code "143") (name "Net-(RGB1C-C)") (class "Default")
      (node (ref "R2") (pin "2") (pinfunction "2_2") (pintype "passive"))
      (node (ref "RGB1") (pin "3") (pinfunction "C_3") (pintype "passive"))
    )
    (net (code "144") (name "Net-(U$2-CC1)") (class "Default")
      (node (ref "R38") (pin "2") (pinfunction "2_2") (pintype "passive"))
      (node (ref "U$2") (pin "3") (pinfunction "CC1_3") (pintype "bidirectional"))
    )
    (net (code "145") (name "Net-(U$2-CC2)") (class "Default")
      (node (ref "R37") (pin "2") (pinfunction "2_2") (pintype "passive"))
      (node (ref "U$2") (pin "4") (pinfunction "CC2_4") (pintype "bidirectional"))
    )
    (net (code "146") (name "Net-(U$2-VBUS1)") (class "Default")
      (node (ref "F2") (pin "1") (pinfunction "1_1") (pintype "passive"))
      (node (ref "U$2") (pin "2") (pinfunction "VBUS1_2") (pintype "bidirectional"))
      (node (ref "U$2") (pin "5") (pinfunction "VBUS2_5") (pintype "bidirectional"))
    )
    (net (code "147") (name "Net-(V1-D)") (class "Default")
      (node (ref "R2") (pin "1") (pinfunction "1_1") (pintype "passive"))
      (node (ref "V1") (pin "3") (pinfunction "D_3") (pintype "passive"))
    )
    (net (code "148") (name "Net-(V2-D)") (class "Default")
      (node (ref "R5") (pin "1") (pinfunction "1_1") (pintype "passive"))
      (node (ref "V2") (pin "3") (pinfunction "D_3") (pintype "passive"))
    )
    (net (code "149") (name "Net-(V3-D)") (class "Default")
      (node (ref "R7") (pin "1") (pinfunction "1_1") (pintype "passive"))
      (node (ref "V3") (pin "3") (pinfunction "D_3") (pintype "passive"))
    )
    (net (code "150") (name "Net-(V5-D)") (class "Default")
      (node (ref "R36") (pin "1") (pinfunction "1_1") (pintype "passive"))
      (node (ref "V5") (pin "3") (pinfunction "D_3") (pintype "passive"))
    )
    (net (code "151") (name "Net-(V6-D)") (class "Default")
      (node (ref "R35") (pin "1") (pinfunction "1_1") (pintype "passive"))
      (node (ref "V6") (pin "3") (pinfunction "D_3") (pintype "passive"))
    )
    (net (code "152") (name "Net-(V7-D)") (class "Default")
      (node (ref "R34") (pin "1") (pinfunction "1_1") (pintype "passive"))
      (node (ref "V7") (pin "3") (pinfunction "D_3") (pintype "passive"))
    )
    (net (code "153") (name "Net-(V8-D)") (class "Default")
      (node (ref "R33") (pin "1") (pinfunction "1_1") (pintype "passive"))
      (node (ref "V8") (pin "3") (pinfunction "D_3") (pintype "passive"))
    )
    (net (code "154") (name "Net-(V9-D)") (class "Default")
      (node (ref "R32") (pin "1") (pinfunction "1_1") (pintype "passive"))
      (node (ref "V9") (pin "3") (pinfunction "D_3") (pintype "passive"))
    )
    (net (code "155") (name "Net-(V10-D)") (class "Default")
      (node (ref "R31") (pin "1") (pinfunction "1_1") (pintype "passive"))
      (node (ref "V10") (pin "3") (pinfunction "D_3") (pintype "passive"))
    )
    (net (code "156") (name "Net-(V11-D)") (class "Default")
      (node (ref "R30") (pin "1") (pinfunction "1_1") (pintype "passive"))
      (node (ref "V11") (pin "3") (pinfunction "D_3") (pintype "passive"))
    )
    (net (code "157") (name "Net-(V12-D)") (class "Default")
      (node (ref "R29") (pin "1") (pinfunction "1_1") (pintype "passive"))
      (node (ref "V12") (pin "3") (pinfunction "D_3") (pintype "passive"))
    )
    (net (code "158") (name "Net-(V13-D)") (class "Default")
      (node (ref "R24") (pin "1") (pinfunction "1_1") (pintype "passive"))
      (node (ref "V13") (pin "3") (pinfunction "D_3") (pintype "passive"))
    )
    (net (code "159") (name "Net-(V14-D)") (class "Default")
      (node (ref "R25") (pin "1") (pinfunction "1_1") (pintype "passive"))
      (node (ref "V14") (pin "3") (pinfunction "D_3") (pintype "passive"))
    )
    (net (code "160") (name "Net-(V15-D)") (class "Default")
      (node (ref "R22") (pin "1") (pinfunction "1_1") (pintype "passive"))
      (node (ref "V15") (pin "3") (pinfunction "D_3") (pintype "passive"))
    )
    (net (code "161") (name "Net-(V16-D)") (class "Default")
      (node (ref "R23") (pin "1") (pinfunction "1_1") (pintype "passive"))
      (node (ref "V16") (pin "3") (pinfunction "D_3") (pintype "passive"))
    )
    (net (code "162") (name "Net-(V17-D)") (class "Default")
      (node (ref "R20") (pin "1") (pinfunction "1_1") (pintype "passive"))
      (node (ref "V17") (pin "3") (pinfunction "D_3") (pintype "passive"))
    )
    (net (code "163") (name "Net-(V18-D)") (class "Default")
      (node (ref "R21") (pin "1") (pinfunction "1_1") (pintype "passive"))
      (node (ref "V18") (pin "3") (pinfunction "D_3") (pintype "passive"))
    )
    (net (code "164") (name "Net-(V19-D)") (class "Default")
      (node (ref "R18") (pin "1") (pinfunction "1_1") (pintype "passive"))
      (node (ref "V19") (pin "3") (pinfunction "D_3") (pintype "passive"))
    )
    (net (code "165") (name "Net-(V20-D)") (class "Default")
      (node (ref "R19") (pin "1") (pinfunction "1_1") (pintype "passive"))
      (node (ref "V20") (pin "3") (pinfunction "D_3") (pintype "passive"))
    )
    (net (code "166") (name "VCC") (class "Default")
      (node (ref "C12") (pin "1") (pinfunction "1_1") (pintype "passive"))
      (node (ref "C14") (pin "+") (pinfunction "+_+") (pintype "passive"))
      (node (ref "C16") (pin "1") (pinfunction "1_1") (pintype "passive"))
      (node (ref "C20") (pin "1") (pinfunction "1_1") (pintype "passive"))
      (node (ref "C24") (pin "+") (pinfunction "+_+") (pintype "passive"))
      (node (ref "C25") (pin "+") (pinfunction "+_+") (pintype "passive"))
      (node (ref "C26") (pin "1") (pinfunction "1_1") (pintype "passive"))
      (node (ref "C4") (pin "1") (pinfunction "1_1") (pintype "passive"))
      (node (ref "C5") (pin "1") (pinfunction "1_1") (pintype "passive"))
      (node (ref "C6") (pin "1") (pinfunction "1_1") (pintype "passive"))
      (node (ref "C7") (pin "1") (pinfunction "1_1") (pintype "passive"))
      (node (ref "H0") (pin "A") (pinfunction "A_A") (pintype "passive"))
      (node (ref "H1") (pin "A") (pinfunction "A_A") (pintype "passive"))
      (node (ref "H10") (pin "A") (pinfunction "A_A") (pintype "passive"))
      (node (ref "H11") (pin "A") (pinfunction "A_A") (pintype "passive"))
      (node (ref "H12") (pin "A") (pinfunction "A_A") (pintype "passive"))
      (node (ref "H13") (pin "A") (pinfunction "A_A") (pintype "passive"))
      (node (ref "H14") (pin "A") (pinfunction "A_A") (pintype "passive"))
      (node (ref "H15") (pin "A") (pinfunction "A_A") (pintype "passive"))
      (node (ref "H2") (pin "A") (pinfunction "A_A") (pintype "passive"))
      (node (ref "H3") (pin "A") (pinfunction "A_A") (pintype "passive"))
      (node (ref "H4") (pin "A") (pinfunction "A_A") (pintype "passive"))
      (node (ref "H5") (pin "A") (pinfunction "A_A") (pintype "passive"))
      (node (ref "H6") (pin "A") (pinfunction "A_A") (pintype "passive"))
      (node (ref "H7") (pin "A") (pinfunction "A_A") (pintype "passive"))
      (node (ref "H8") (pin "A") (pinfunction "A_A") (pintype "passive"))
      (node (ref "H9") (pin "A") (pinfunction "A_A") (pintype "passive"))
      (node (ref "IC1") (pin "14") (pinfunction "VCC_14") (pintype "power_in"))
      (node (ref "IC2") (pin "10") (pinfunction "VCC_10") (pintype "power_in"))
      (node (ref "IC2") (pin "31") (pinfunction "VCC1_31") (pintype "power_in"))
      (node (ref "IC2") (pin "61") (pinfunction "VCC2_61") (pintype "power_in"))
      (node (ref "IC2") (pin "80") (pinfunction "VCC3_80") (pintype "power_in"))
      (node (ref "IC3") (pin "1") (pinfunction "VCC_1") (pintype "power_in"))
      (node (ref "IC4") (pin "1") (pinfunction "VCC_1") (pintype "power_in"))
      (node (ref "IC5") (pin "16") (pinfunction "VCC_16") (pintype "power_in"))
      (node (ref "IC6") (pin "1") (pinfunction "IN_1") (pintype "input"))
      (node (ref "IC6") (pin "3") (pinfunction "ON/~{OFF}_3") (pintype "input"))
      (node (ref "JP1") (pin "2") (pinfunction "2_2") (pintype "passive"))
      (node (ref "JP2") (pin "2") (pinfunction "2_2") (pintype "passive"))
      (node (ref "JP3") (pin "2") (pinfunction "2_2") (pintype "passive"))
      (node (ref "JTAG") (pin "4") (pinfunction "4_4") (pintype "passive"))
      (node (ref "L1") (pin "1") (pinfunction "1_1") (pintype "passive"))
      (node (ref "Q10") (pin "2") (pinfunction "S_2") (pintype "passive"))
      (node (ref "Q3") (pin "2") (pinfunction "S_2") (pintype "passive"))
      (node (ref "Q4") (pin "2") (pinfunction "S_2") (pintype "passive"))
      (node (ref "Q5") (pin "2") (pinfunction "S_2") (pintype "passive"))
      (node (ref "Q6") (pin "2") (pinfunction "S_2") (pintype "passive"))
      (node (ref "Q7") (pin "2") (pinfunction "S_2") (pintype "passive"))
      (node (ref "Q8") (pin "2") (pinfunction "S_2") (pintype "passive"))
      (node (ref "Q9") (pin "2") (pinfunction "S_2") (pintype "passive"))
      (node (ref "R1") (pin "3") (pinfunction "E_3") (pintype "passive"))
      (node (ref "R10") (pin "2") (pinfunction "2_2") (pintype "passive"))
      (node (ref "R11") (pin "2") (pinfunction "2_2") (pintype "passive"))
      (node (ref "R17") (pin "2") (pinfunction "2_2") (pintype "passive"))
      (node (ref "R3") (pin "1") (pinfunction "1_1") (pintype "passive"))
      (node (ref "R4") (pin "1") (pinfunction "1_1") (pintype "passive"))
      (node (ref "R45") (pin "2") (pinfunction "2_2") (pintype "passive"))
      (node (ref "R6") (pin "3") (pinfunction "E_3") (pintype "passive"))
      (node (ref "R8") (pin "2") (pinfunction "2_2") (pintype "passive"))
      (node (ref "R9") (pin "2") (pinfunction "2_2") (pintype "passive"))
      (node (ref "RGB1") (pin "4") (pinfunction "A_4") (pintype "passive"))
      (node (ref "RGB1") (pin "5") (pinfunction "A_5") (pintype "passive"))
      (node (ref "RGB1") (pin "6") (pinfunction "A_6") (pintype "passive"))
      (node (ref "S10") (pin "1") (pinfunction "S_1") (pintype "passive"))
      (node (ref "S11") (pin "1") (pinfunction "S_1") (pintype "passive"))
      (node (ref "S12") (pin "1") (pinfunction "S_1") (pintype "passive"))
      (node (ref "S5") (pin "1") (pinfunction "S_1") (pintype "passive"))
      (node (ref "S6") (pin "1") (pinfunction "S_1") (pintype "passive"))
      (node (ref "S7") (pin "1") (pinfunction "S_1") (pintype "passive"))
      (node (ref "S8") (pin "1") (pinfunction "S_1") (pintype "passive"))
      (node (ref "S9") (pin "1") (pinfunction "S_1") (pintype "passive"))
      (node (ref "U$1") (pin "5") (pinfunction "U/D+_5") (pintype "bidirectional"))
      (node (ref "U$1") (pin "8") (pinfunction "L/R-_8") (pintype "bidirectional"))
      (node (ref "U$3") (pin "C") (pinfunction "C_C") (pintype "passive"))
      (node (ref "U1") (pin "1") (pinfunction "+VS_1") (pintype "passive"))
      (node (ref "X1") (pin "9") (pinfunction "KL_9") (pintype "passive"))
      (node (ref "X3") (pin "14") (pinfunction "KL_14") (pintype "passive"))
      (node (ref "X4") (pin "9") (pinfunction "KL_9") (pintype "passive"))
      (node (ref "X5") (pin "9") (pinfunction "KL_9") (pintype "passive"))
    )
    (net (code "167") (name "unconnected-(IC2-(ALE)PG2-Pad70)") (class "Default")
      (node (ref "IC2") (pin "70") (pinfunction "(ALE)PG2_70") (pintype "bidirectional"))
    )
    (net (code "168") (name "unconnected-(IC2-(CLKO{slash}ICP3{slash}INT7)PE7-Pad9)") (class "Default")
      (node (ref "IC2") (pin "9") (pinfunction "(CLKO/ICP3/INT7)PE7_9") (pintype "bidirectional"))
    )
    (net (code "169") (name "unconnected-(IC2-(T3{slash}INT6)PE6-Pad8)") (class "Default")
      (node (ref "IC2") (pin "8") (pinfunction "(T3/INT6)PE6_8") (pintype "bidirectional"))
    )
    (net (code "170") (name "unconnected-(IC2-PH0(RXD2)-Pad12)") (class "Default")
      (node (ref "IC2") (pin "12") (pinfunction "PH0(RXD2)_12") (pintype "bidirectional"))
    )
    (net (code "171") (name "unconnected-(IC2-PH1(TXD2)-Pad13)") (class "Default")
      (node (ref "IC2") (pin "13") (pinfunction "PH1(TXD2)_13") (pintype "bidirectional"))
    )
    (net (code "172") (name "unconnected-(IC2-PH2(XCK2)-Pad14)") (class "Default")
      (node (ref "IC2") (pin "14") (pinfunction "PH2(XCK2)_14") (pintype "bidirectional"))
    )
    (net (code "173") (name "unconnected-(IC2-PH6(OC2B)-Pad18)") (class "Default")
      (node (ref "IC2") (pin "18") (pinfunction "PH6(OC2B)_18") (pintype "bidirectional"))
    )
    (net (code "174") (name "unconnected-(IC2-PH7(T4)-Pad27)") (class "Default")
      (node (ref "IC2") (pin "27") (pinfunction "PH7(T4)_27") (pintype "bidirectional"))
    )
    (net (code "175") (name "unconnected-(IC2-PJ7-Pad79)") (class "Default")
      (node (ref "IC2") (pin "79") (pinfunction "PJ7_79") (pintype "bidirectional"))
    )
    (net (code "176") (name "unconnected-(LCD1-D0(SOD)-Pad7)") (class "Default")
      (node (ref "LCD1") (pin "7") (pinfunction "D0(SOD)_7") (pintype "no_connect"))
    )
    (net (code "177") (name "unconnected-(LCD1-D1-Pad8)") (class "Default")
      (node (ref "LCD1") (pin "8") (pinfunction "D1_8") (pintype "no_connect"))
    )
    (net (code "178") (name "unconnected-(LCD1-D2-Pad9)") (class "Default")
      (node (ref "LCD1") (pin "9") (pinfunction "D2_9") (pintype "no_connect"))
    )
    (net (code "179") (name "unconnected-(LCD1-D3-Pad10)") (class "Default")
      (node (ref "LCD1") (pin "10") (pinfunction "D3_10") (pintype "no_connect"))
    )
    (net (code "180") (name "unconnected-(LCD1-D4-Pad11)") (class "Default")
      (node (ref "LCD1") (pin "11") (pinfunction "D4_11") (pintype "no_connect"))
    )
    (net (code "181") (name "unconnected-(LCD1-D5-Pad12)") (class "Default")
      (node (ref "LCD1") (pin "12") (pinfunction "D5_12") (pintype "no_connect"))
    )
    (net (code "182") (name "unconnected-(LCD1-D6-Pad13)") (class "Default")
      (node (ref "LCD1") (pin "13") (pinfunction "D6_13") (pintype "no_connect"))
    )
    (net (code "183") (name "unconnected-(LCD1-D7-Pad14)") (class "Default")
      (node (ref "LCD1") (pin "14") (pinfunction "D7_14") (pintype "no_connect"))
    )
    (net (code "184") (name "unconnected-(LCD1-NC-Pad15)") (class "Default")
      (node (ref "LCD1") (pin "15") (pinfunction "NC_15") (pintype "no_connect"))
    )
    (net (code "185") (name "unconnected-(LCD1-RESET-Pad16)") (class "Default")
      (node (ref "LCD1") (pin "16") (pinfunction "RESET_16") (pintype "no_connect"))
    )
  )
)
